# M_2_SoM_breakout_board_V1_0.net
KiCad netlist of a schematic drawn in EAGLE
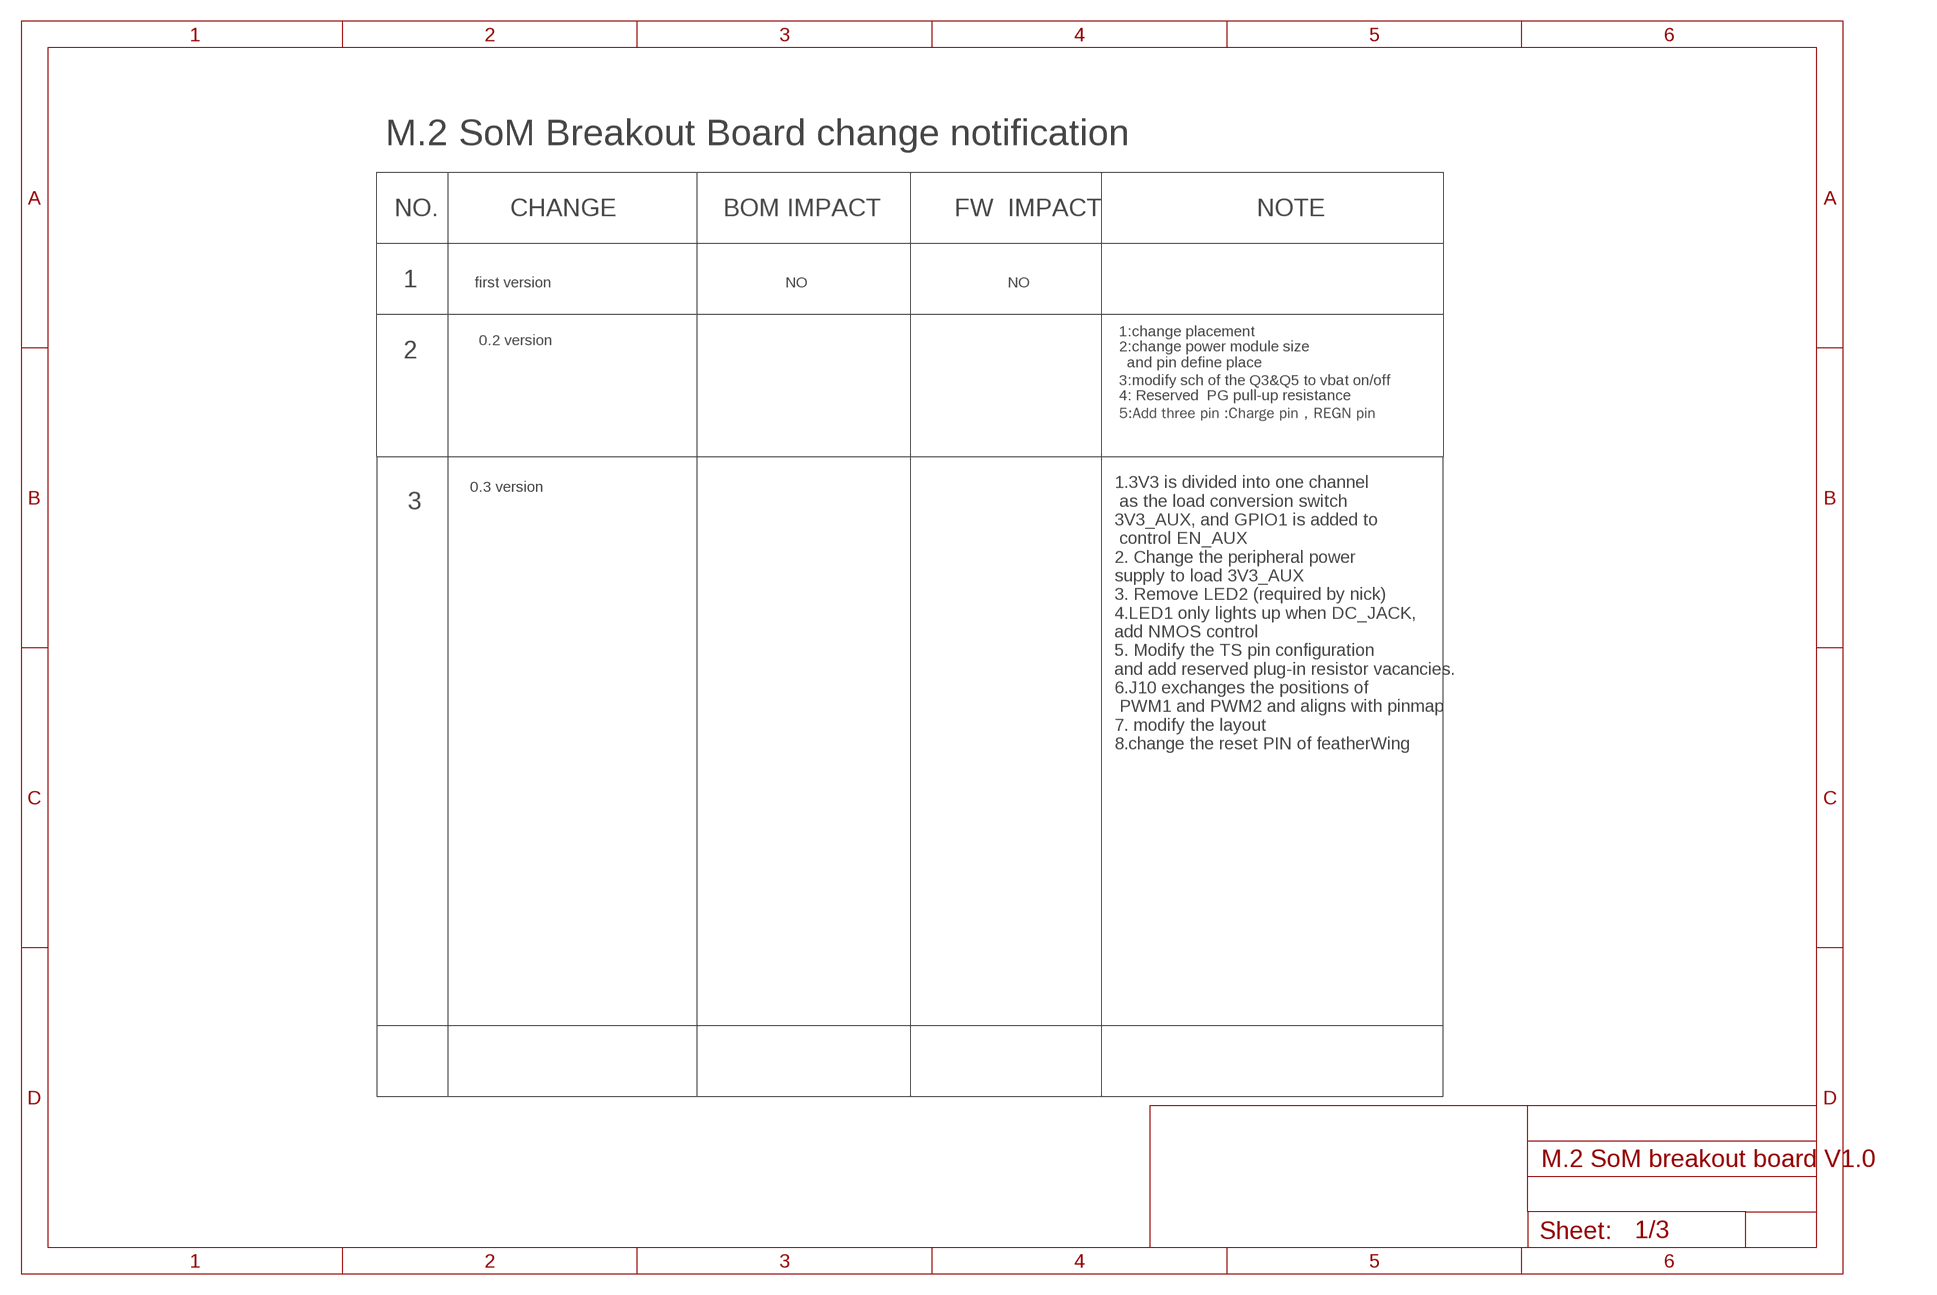
[diagram p0: schematic, sheet 1]
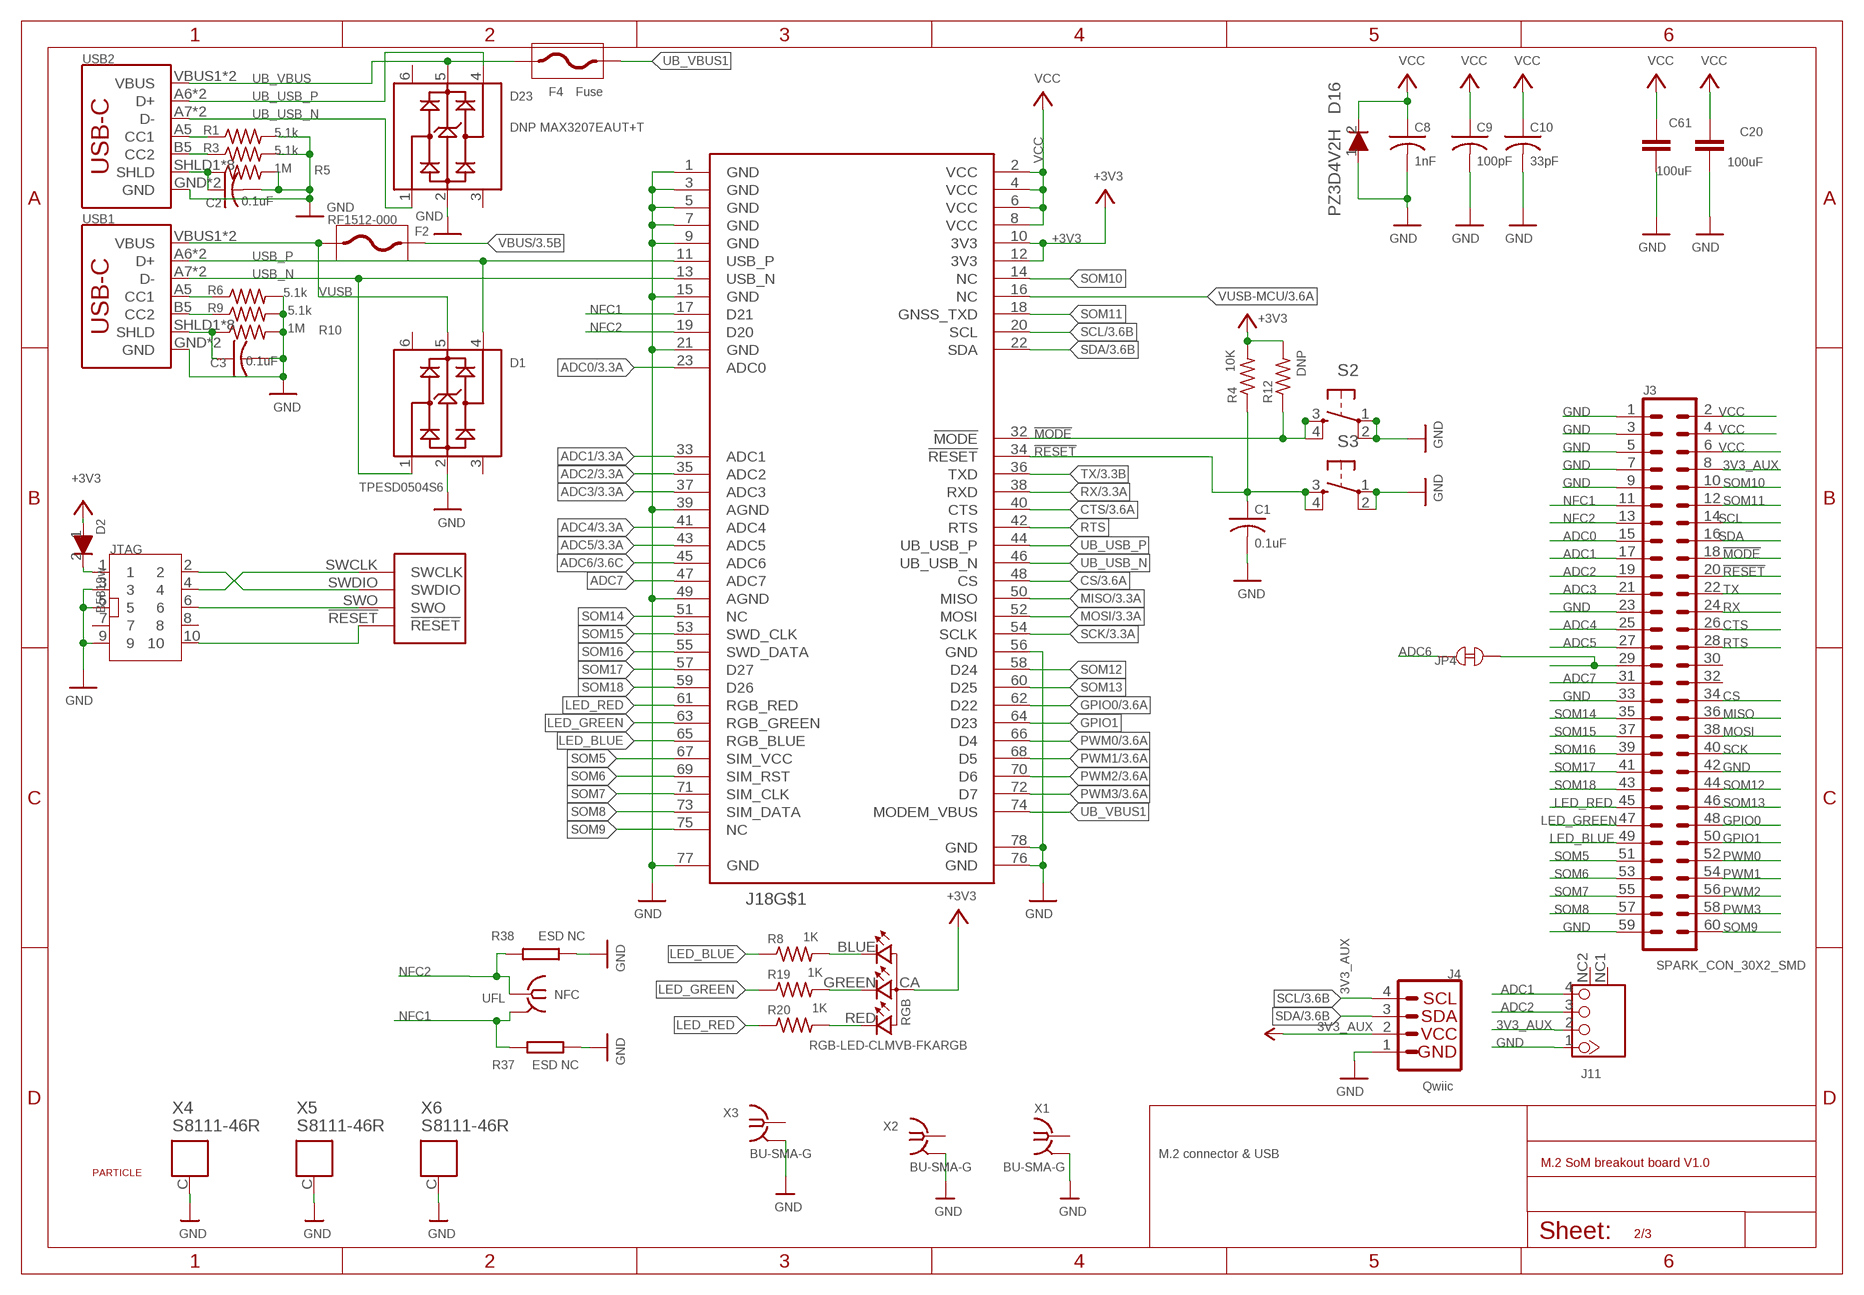
[diagram p1: schematic, sheet 2]
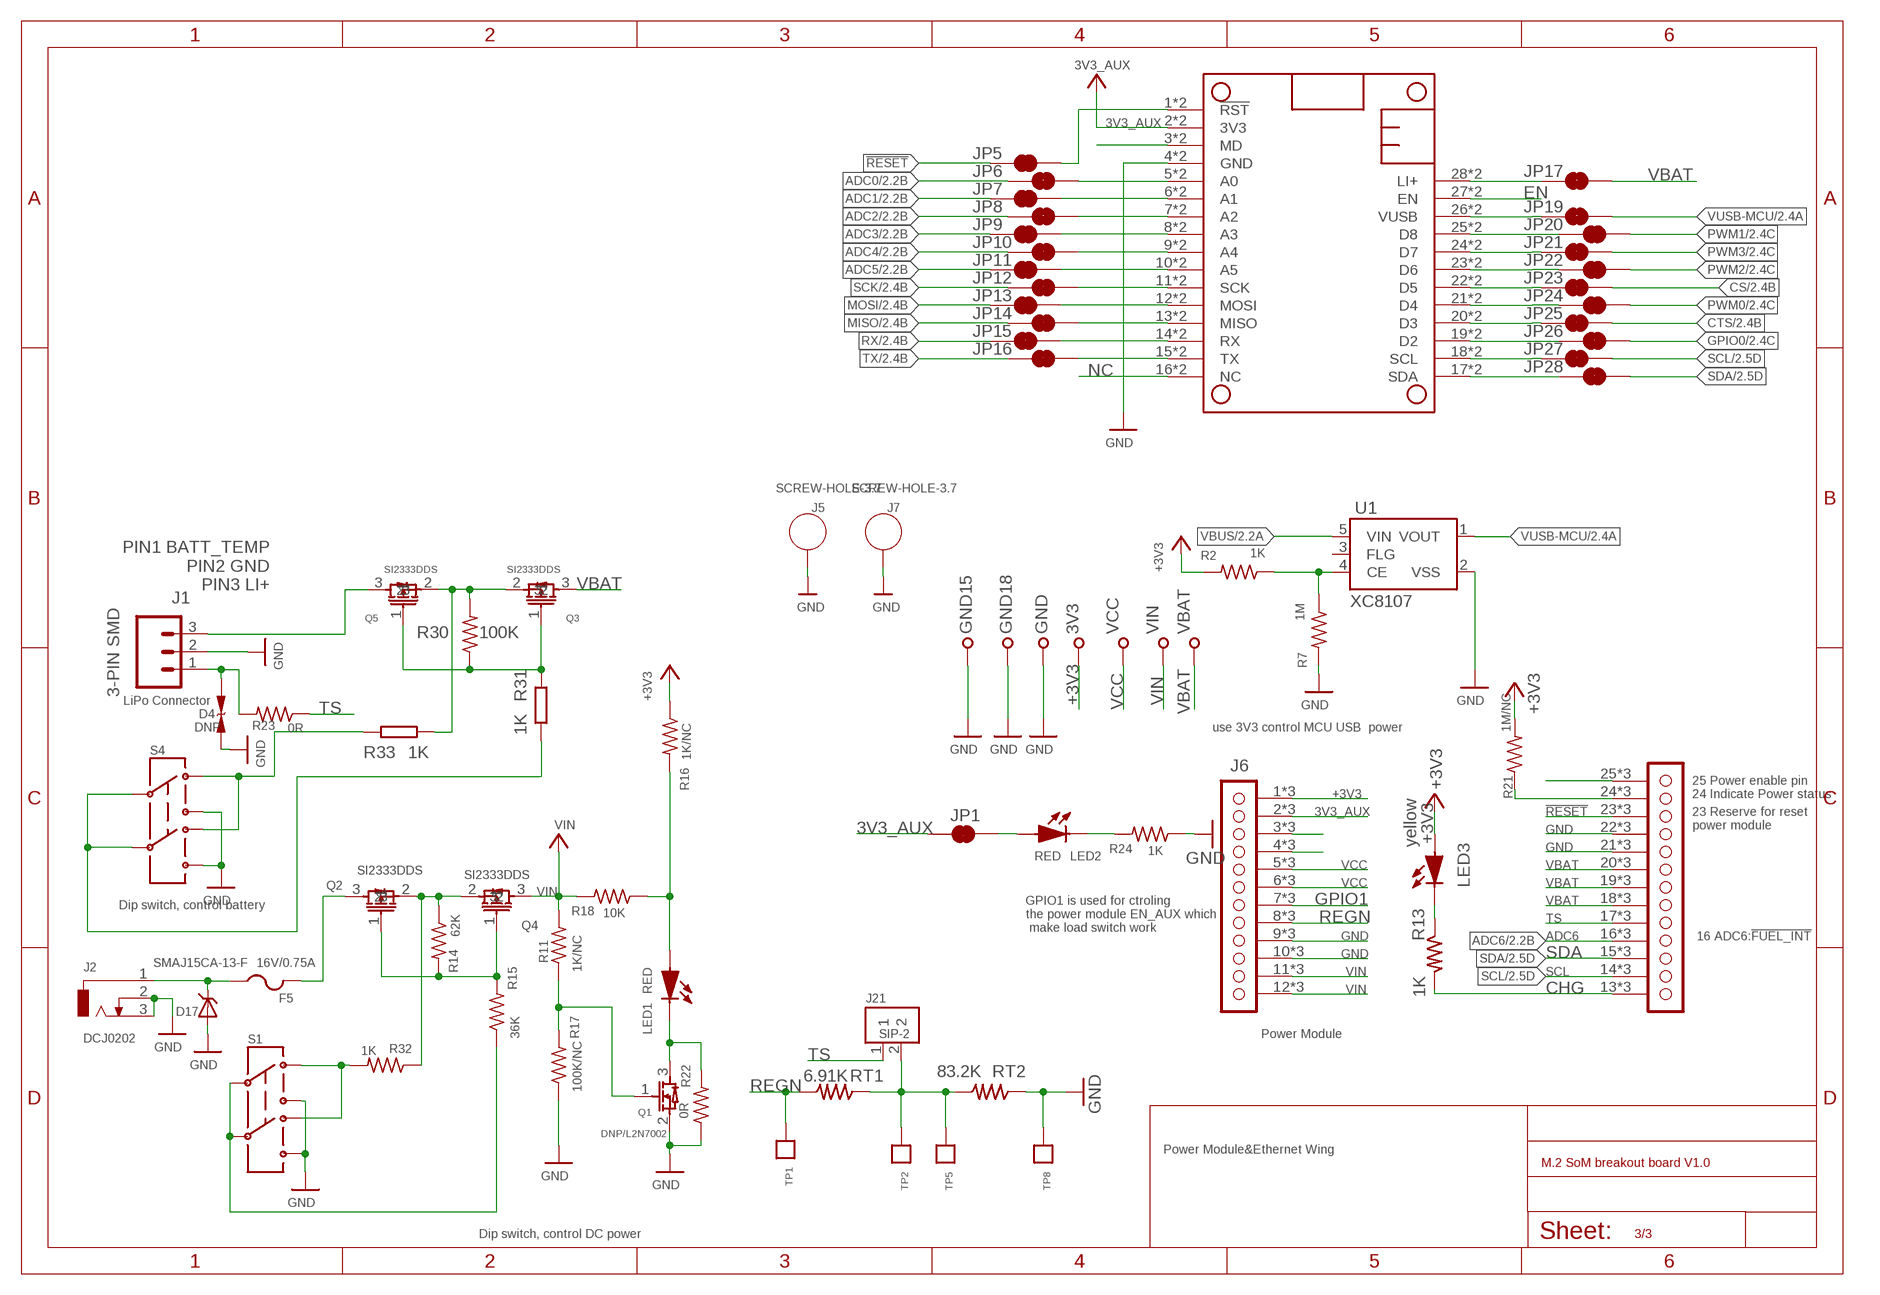
[diagram p2: schematic, sheet 3]

(export (version "E")
  (design (tool "Eeschema 10.0.6"))
  (components
    (comp (ref "C1")
      (value "0.1uF")
      (footprint "eagle-import:C0402_B")
      (libsource (lib "eagle-import") (part "C-US"))
    )
    (comp (ref "C2")
      (value "0.1uF")
      (footprint "eagle-import:C0402_B")
      (libsource (lib "eagle-import") (part "C-US"))
    )
    (comp (ref "C3")
      (value "0.1uF")
      (footprint "eagle-import:C0402_B")
      (libsource (lib "eagle-import") (part "C-US"))
    )
    (comp (ref "C8")
      (value "1nF")
      (footprint "eagle-import:C0402_B")
      (libsource (lib "eagle-import") (part "C-US"))
    )
    (comp (ref "C9")
      (value "100pF")
      (footprint "eagle-import:C0402_B")
      (libsource (lib "eagle-import") (part "C-US"))
    )
    (comp (ref "C10")
      (value "33pF")
      (footprint "eagle-import:C0402_B")
      (libsource (lib "eagle-import") (part "C-US"))
    )
    (comp (ref "C20")
      (value "100uF")
      (footprint "eagle-import:C1206K")
      (libsource (lib "eagle-import") (part "C-EUC1206K"))
    )
    (comp (ref "C61")
      (value "100uF")
      (footprint "eagle-import:C1206K")
      (libsource (lib "eagle-import") (part "C-EUC1206K"))
    )
    (comp (ref "D1")
      (value "TPESD0504S6")
      (footprint "eagle-import:SOT23-6")
      (fields (field (name "MFG") "MAXIM") (field (name "MPN") "MAX3207EAUT+T"))
      (libsource (lib "eagle-import") (part "MAX3207EAUT+T"))
    )
    (comp (ref "D2")
      (value "B5819w")
      (footprint "eagle-import:SOD-123")
      (libsource (lib "eagle-import") (part "DIODESOD123"))
    )
    (comp (ref "D16")
      (value "PZ3D4V2H")
      (footprint "eagle-import:SOD-323")
      (libsource (lib "eagle-import") (part "DIODESOD323"))
    )
    (comp (ref "D23")
      (value "DNP MAX3207EAUT+T")
      (footprint "eagle-import:SOT23-6")
      (fields (field (name "MFG") "MAXIM") (field (name "MPN") "MAX3207EAUT+T"))
      (libsource (lib "eagle-import") (part "MAX3207EAUT+T"))
    )
    (comp (ref "F2")
      (value "RF1512-000")
      (footprint "eagle-import:F0805")
      (libsource (lib "eagle-import") (part "FUSE"))
    )
    (comp (ref "F4")
      (value "Fuse")
      (footprint "eagle-import:F0805")
      (libsource (lib "eagle-import") (part "FUSE"))
    )
    (comp (ref "J3")
      (value "SPARK_CON_30X2_SMD")
      (footprint "eagle-import:SPARK_CON_30X2_SMD")
      (libsource (lib "eagle-import") (part "SPARK_CON_30X2_SMD"))
    )
    (comp (ref "J4")
      (value "QWIIC_CONNECTORJS-1MM")
      (footprint "eagle-import:1X04_1MM_RA")
      (libsource (lib "eagle-import") (part "QWIIC_CONNECTORJS-1MM"))
    )
    (comp (ref "J11")
      (value "WAFER-HY2.0-4PWB")
      (footprint "eagle-import:M.2-SOM-BREAKOUT-BOARD-V0.2-0228_WAFER-HY2.0-4PWB")
      (libsource (lib "eagle-import") (part "M.2-SOM-BREAKOUT-BOARD-V0.2-0228_WAFER-HY2.0-4PWB"))
    )
    (comp (ref "J18")
      (value "PARTICLE-STUDIOS_M_SERIES_M.2KEY")
      (footprint "eagle-import:PARTICLE-STUDIOS_PARTICLE_M.2EKEY_3.65MM_DRILL")
      (libsource (lib "eagle-import") (part "PARTICLE-STUDIOS_M_SERIES_M.2KEY"))
    )
    (comp (ref "JP4")
      (value "TP_SHORT")
      (footprint "eagle-import:TP_SHORT")
      (libsource (lib "eagle-import") (part "TP_SHORT"))
    )
    (comp (ref "JTAG")
      (value "CONN5X2")
      (footprint "eagle-import:CONN5X2_1.27")
      (fields (field (name "MFG") "KAWEEI") (field (name "MPN") "P6014A-M2GC-030-10"))
      (libsource (lib "eagle-import") (part "CONN5X2"))
    )
    (comp (ref "NFC")
      (value "UFL")
      (footprint "eagle-import:IPEX-20279-001E")
      (libsource (lib "eagle-import") (part "IPEX-20279-001E"))
    )
    (comp (ref "R1")
      (value "5.1k")
      (footprint "eagle-import:R0402_B")
      (libsource (lib "eagle-import") (part "R-US_"))
    )
    (comp (ref "R3")
      (value "5.1k")
      (footprint "eagle-import:R0402_B")
      (libsource (lib "eagle-import") (part "R-US_"))
    )
    (comp (ref "R4")
      (value "10K")
      (footprint "eagle-import:R0402_B")
      (libsource (lib "eagle-import") (part "R-US_"))
    )
    (comp (ref "R5")
      (value "1M")
      (footprint "eagle-import:R0402_B")
      (libsource (lib "eagle-import") (part "R-US_"))
    )
    (comp (ref "R6")
      (value "5.1k")
      (footprint "eagle-import:R0402_B")
      (libsource (lib "eagle-import") (part "R-US_"))
    )
    (comp (ref "R8")
      (value "1K")
      (footprint "eagle-import:R0402_B")
      (libsource (lib "eagle-import") (part "R-US_"))
    )
    (comp (ref "R9")
      (value "5.1k")
      (footprint "eagle-import:R0402_B")
      (libsource (lib "eagle-import") (part "R-US_"))
    )
    (comp (ref "R10")
      (value "1M")
      (footprint "eagle-import:R0402_B")
      (libsource (lib "eagle-import") (part "R-US_"))
    )
    (comp (ref "R12")
      (value "DNP")
      (footprint "eagle-import:R0402_B")
      (libsource (lib "eagle-import") (part "R-US_"))
    )
    (comp (ref "R19")
      (value "1K")
      (footprint "eagle-import:R0402_B")
      (libsource (lib "eagle-import") (part "R-US_"))
    )
    (comp (ref "R20")
      (value "1K")
      (footprint "eagle-import:R0402_B")
      (libsource (lib "eagle-import") (part "R-US_"))
    )
    (comp (ref "R37")
      (value "ESD NC")
      (footprint "eagle-import:R-0402S")
      (libsource (lib "eagle-import") (part "RES0402S"))
    )
    (comp (ref "R38")
      (value "ESD NC")
      (footprint "eagle-import:R-0402S")
      (libsource (lib "eagle-import") (part "RES0402S"))
    )
    (comp (ref "RGB")
      (value "RGB-LED-CLMVB-FKARGB")
      (footprint "eagle-import:PLCC4-2MM-RGB")
      (libsource (lib "eagle-import") (part "RGB-LED-CLMVB-FKARGB"))
    )
    (comp (ref "S2")
      (value "TAC_SWITCH")
      (footprint "eagle-import:TACTILE_SWITCH_4.2_3.2")
      (libsource (lib "eagle-import") (part "TAC_SWITCH"))
    )
    (comp (ref "S3")
      (value "TAC_SWITCH")
      (footprint "eagle-import:TACTILE_SWITCH_4.2_3.2")
      (libsource (lib "eagle-import") (part "TAC_SWITCH"))
    )
    (comp (ref "U$6")
      (value "PARTICLE-LOGO")
      (footprint "eagle-import:PARTICLE-LOGO")
      (libsource (lib "eagle-import") (part "PARTICLE-LOGO"))
    )
    (comp (ref "USB1")
      (value "USB_C16PIN")
      (footprint "eagle-import:USB-C-16P")
      (libsource (lib "eagle-import") (part "USB_C16PIN"))
    )
    (comp (ref "USB2")
      (value "USB_C16PIN")
      (footprint "eagle-import:USB-C-16P")
      (libsource (lib "eagle-import") (part "USB_C16PIN"))
    )
    (comp (ref "X1")
      (value "BU-SMA-G")
      (footprint "eagle-import:BU-SMA-G")
      (libsource (lib "eagle-import") (part "BU-SMA-G"))
    )
    (comp (ref "X2")
      (value "BU-SMA-G")
      (footprint "eagle-import:BU-SMA-G")
      (libsource (lib "eagle-import") (part "BU-SMA-G"))
    )
    (comp (ref "X3")
      (value "BU-SMA-G")
      (footprint "eagle-import:BU-SMA-G")
      (libsource (lib "eagle-import") (part "BU-SMA-G"))
    )
    (comp (ref "X4")
      (value "S8111-46R")
      (footprint "eagle-import:S8111-46R")
      (libsource (lib "eagle-import") (part "S8111-46R"))
    )
    (comp (ref "X5")
      (value "S8111-46R")
      (footprint "eagle-import:S8111-46R")
      (libsource (lib "eagle-import") (part "S8111-46R"))
    )
    (comp (ref "X6")
      (value "S8111-46R")
      (footprint "eagle-import:S8111-46R")
      (libsource (lib "eagle-import") (part "S8111-46R"))
    )
    (comp (ref "3V3")
      (value "TP-S2751-46R")
      (footprint "eagle-import:S2751-46R")
      (libsource (lib "eagle-import") (part "TP-S2751-46R"))
    )
    (comp (ref "D4")
      (value "DNP")
      (footprint "eagle-import:C0402")
      (libsource (lib "eagle-import") (part "ESD"))
    )
    (comp (ref "D17")
      (value "SMAJ15CA-13-F")
      (footprint "eagle-import:SMADIODE")
      (libsource (lib "eagle-import") (part "DIODE-ZENER"))
    )
    (comp (ref "F5")
      (value "16V/0.75A")
      (footprint "eagle-import:1812")
      (libsource (lib "eagle-import") (part "PTCFUSE-1812"))
    )
    (comp (ref "GND")
      (value "TP-S2751-46R")
      (footprint "eagle-import:S2751-46R")
      (libsource (lib "eagle-import") (part "TP-S2751-46R"))
    )
    (comp (ref "GND15")
      (value "TP-S2751-46R")
      (footprint "eagle-import:S2751-46R")
      (libsource (lib "eagle-import") (part "TP-S2751-46R"))
    )
    (comp (ref "GND18")
      (value "TP-S2751-46R")
      (footprint "eagle-import:S2751-46R")
      (libsource (lib "eagle-import") (part "TP-S2751-46R"))
    )
    (comp (ref "J1")
      (value "3-PIN SMD")
      (footprint "eagle-import:JST-3-SMD")
      (libsource (lib "eagle-import") (part "CONN_03JST-SMD"))
    )
    (comp (ref "J2")
      (value "DCJ0202")
      (footprint "eagle-import:DCJ0202")
      (libsource (lib "eagle-import") (part "DCJ0202"))
    )
    (comp (ref "J5")
      (value "SCREW-HOLE-3.7")
      (footprint "eagle-import:SCREW-HOLE-3.7")
      (libsource (lib "eagle-import") (part "SCREW-HOLE-3.7"))
    )
    (comp (ref "J6")
      (value "M.2-SOM-BREAKOUT-BOARD-V0.3_M.2-SOM-BREAKOUT-BOARD-V0.2-0228_PARTICLE-SZ_PARTICLE-POWER-MODULE")
      (footprint "eagle-import:M.2-SOM-BREAKOUT-BOARD-V0.3_M.2-SOM-BREAKOUT-BOARD-V0.2-0228_PARTICLE-SZ_PARTICLE-POWER-MODULE")
      (libsource (lib "eagle-import") (part "M.2-SOM-BREAKOUT-BOARD-V0.3_M.2-SOM-BREAKOUT-BOARD-V0.2-0228_PARTICLE-SZ_PARTICLE-POWER-MODULE"))
    )
    (comp (ref "J7")
      (value "SCREW-HOLE-3.7")
      (footprint "eagle-import:SCREW-HOLE-3.7")
      (libsource (lib "eagle-import") (part "SCREW-HOLE-3.7"))
    )
    (comp (ref "J21")
      (value "SIP-2")
      (footprint "eagle-import:SIP-2")
      (libsource (lib "eagle-import") (part "SIP-2"))
    )
    (comp (ref "JP1")
      (value "JUMPER-SMT_2_NC_TRACE_NO-SILK")
      (footprint "eagle-import:SMT-JUMPER_2_NC_TRACE_NO-SILK")
      (libsource (lib "eagle-import") (part "JUMPER-SMT_2_NC_TRACE_NO-SILK"))
    )
    (comp (ref "JP5")
      (value "JUMPER-SMT_2_NC_TRACE_NO-SILK")
      (footprint "eagle-import:SMT-JUMPER_2_NC_TRACE_NO-SILK")
      (libsource (lib "eagle-import") (part "JUMPER-SMT_2_NC_TRACE_NO-SILK"))
    )
    (comp (ref "JP6")
      (value "JUMPER-SMT_2_NC_TRACE_NO-SILK")
      (footprint "eagle-import:SMT-JUMPER_2_NC_TRACE_NO-SILK")
      (libsource (lib "eagle-import") (part "JUMPER-SMT_2_NC_TRACE_NO-SILK"))
    )
    (comp (ref "JP7")
      (value "JUMPER-SMT_2_NC_TRACE_NO-SILK")
      (footprint "eagle-import:SMT-JUMPER_2_NC_TRACE_NO-SILK")
      (libsource (lib "eagle-import") (part "JUMPER-SMT_2_NC_TRACE_NO-SILK"))
    )
    (comp (ref "JP8")
      (value "JUMPER-SMT_2_NC_TRACE_NO-SILK")
      (footprint "eagle-import:SMT-JUMPER_2_NC_TRACE_NO-SILK")
      (libsource (lib "eagle-import") (part "JUMPER-SMT_2_NC_TRACE_NO-SILK"))
    )
    (comp (ref "JP9")
      (value "JUMPER-SMT_2_NC_TRACE_NO-SILK")
      (footprint "eagle-import:SMT-JUMPER_2_NC_TRACE_NO-SILK")
      (libsource (lib "eagle-import") (part "JUMPER-SMT_2_NC_TRACE_NO-SILK"))
    )
    (comp (ref "JP10")
      (value "JUMPER-SMT_2_NC_TRACE_NO-SILK")
      (footprint "eagle-import:SMT-JUMPER_2_NC_TRACE_NO-SILK")
      (libsource (lib "eagle-import") (part "JUMPER-SMT_2_NC_TRACE_NO-SILK"))
    )
    (comp (ref "JP11")
      (value "JUMPER-SMT_2_NC_TRACE_NO-SILK")
      (footprint "eagle-import:SMT-JUMPER_2_NC_TRACE_NO-SILK")
      (libsource (lib "eagle-import") (part "JUMPER-SMT_2_NC_TRACE_NO-SILK"))
    )
    (comp (ref "JP12")
      (value "JUMPER-SMT_2_NC_TRACE_NO-SILK")
      (footprint "eagle-import:SMT-JUMPER_2_NC_TRACE_NO-SILK")
      (libsource (lib "eagle-import") (part "JUMPER-SMT_2_NC_TRACE_NO-SILK"))
    )
    (comp (ref "JP13")
      (value "JUMPER-SMT_2_NC_TRACE_NO-SILK")
      (footprint "eagle-import:SMT-JUMPER_2_NC_TRACE_NO-SILK")
      (libsource (lib "eagle-import") (part "JUMPER-SMT_2_NC_TRACE_NO-SILK"))
    )
    (comp (ref "JP14")
      (value "JUMPER-SMT_2_NC_TRACE_NO-SILK")
      (footprint "eagle-import:SMT-JUMPER_2_NC_TRACE_NO-SILK")
      (libsource (lib "eagle-import") (part "JUMPER-SMT_2_NC_TRACE_NO-SILK"))
    )
    (comp (ref "JP15")
      (value "JUMPER-SMT_2_NC_TRACE_NO-SILK")
      (footprint "eagle-import:SMT-JUMPER_2_NC_TRACE_NO-SILK")
      (libsource (lib "eagle-import") (part "JUMPER-SMT_2_NC_TRACE_NO-SILK"))
    )
    (comp (ref "JP16")
      (value "JUMPER-SMT_2_NC_TRACE_NO-SILK")
      (footprint "eagle-import:SMT-JUMPER_2_NC_TRACE_NO-SILK")
      (libsource (lib "eagle-import") (part "JUMPER-SMT_2_NC_TRACE_NO-SILK"))
    )
    (comp (ref "JP17")
      (value "JUMPER-SMT_2_NC_TRACE_NO-SILK")
      (footprint "eagle-import:SMT-JUMPER_2_NC_TRACE_NO-SILK")
      (libsource (lib "eagle-import") (part "JUMPER-SMT_2_NC_TRACE_NO-SILK"))
    )
    (comp (ref "JP19")
      (value "JUMPER-SMT_2_NC_TRACE_NO-SILK")
      (footprint "eagle-import:SMT-JUMPER_2_NC_TRACE_NO-SILK")
      (libsource (lib "eagle-import") (part "JUMPER-SMT_2_NC_TRACE_NO-SILK"))
    )
    (comp (ref "JP20")
      (value "JUMPER-SMT_2_NC_TRACE_NO-SILK")
      (footprint "eagle-import:SMT-JUMPER_2_NC_TRACE_NO-SILK")
      (libsource (lib "eagle-import") (part "JUMPER-SMT_2_NC_TRACE_NO-SILK"))
    )
    (comp (ref "JP21")
      (value "JUMPER-SMT_2_NC_TRACE_NO-SILK")
      (footprint "eagle-import:SMT-JUMPER_2_NC_TRACE_NO-SILK")
      (libsource (lib "eagle-import") (part "JUMPER-SMT_2_NC_TRACE_NO-SILK"))
    )
    (comp (ref "JP22")
      (value "JUMPER-SMT_2_NC_TRACE_NO-SILK")
      (footprint "eagle-import:SMT-JUMPER_2_NC_TRACE_NO-SILK")
      (libsource (lib "eagle-import") (part "JUMPER-SMT_2_NC_TRACE_NO-SILK"))
    )
    (comp (ref "JP23")
      (value "JUMPER-SMT_2_NC_TRACE_NO-SILK")
      (footprint "eagle-import:SMT-JUMPER_2_NC_TRACE_NO-SILK")
      (libsource (lib "eagle-import") (part "JUMPER-SMT_2_NC_TRACE_NO-SILK"))
    )
    (comp (ref "JP24")
      (value "JUMPER-SMT_2_NC_TRACE_NO-SILK")
      (footprint "eagle-import:SMT-JUMPER_2_NC_TRACE_NO-SILK")
      (libsource (lib "eagle-import") (part "JUMPER-SMT_2_NC_TRACE_NO-SILK"))
    )
    (comp (ref "JP25")
      (value "JUMPER-SMT_2_NC_TRACE_NO-SILK")
      (footprint "eagle-import:SMT-JUMPER_2_NC_TRACE_NO-SILK")
      (libsource (lib "eagle-import") (part "JUMPER-SMT_2_NC_TRACE_NO-SILK"))
    )
    (comp (ref "JP26")
      (value "JUMPER-SMT_2_NC_TRACE_NO-SILK")
      (footprint "eagle-import:SMT-JUMPER_2_NC_TRACE_NO-SILK")
      (libsource (lib "eagle-import") (part "JUMPER-SMT_2_NC_TRACE_NO-SILK"))
    )
    (comp (ref "JP27")
      (value "JUMPER-SMT_2_NC_TRACE_NO-SILK")
      (footprint "eagle-import:SMT-JUMPER_2_NC_TRACE_NO-SILK")
      (libsource (lib "eagle-import") (part "JUMPER-SMT_2_NC_TRACE_NO-SILK"))
    )
    (comp (ref "JP28")
      (value "JUMPER-SMT_2_NC_TRACE_NO-SILK")
      (footprint "eagle-import:SMT-JUMPER_2_NC_TRACE_NO-SILK")
      (libsource (lib "eagle-import") (part "JUMPER-SMT_2_NC_TRACE_NO-SILK"))
    )
    (comp (ref "LED1")
      (value "RED")
      (footprint "eagle-import:LED0603")
      (libsource (lib "eagle-import") (part "LED"))
    )
    (comp (ref "LED2")
      (value "RED")
      (footprint "eagle-import:LED0603")
      (libsource (lib "eagle-import") (part "LED"))
    )
    (comp (ref "LED3")
      (value "yellow")
      (footprint "eagle-import:LED0603")
      (libsource (lib "eagle-import") (part "LED"))
    )
    (comp (ref "MS1")
      (value "PARTICLE_MESH_SMTDUAL")
      (footprint "eagle-import:FEATHERWING_SMT2")
      (libsource (lib "eagle-import") (part "PARTICLE_MESH_SMTDUAL"))
    )
    (comp (ref "Q1")
      (value "DNP/L2N7002")
      (footprint "eagle-import:SOT323")
      (libsource (lib "eagle-import") (part "NMOSSOT323"))
    )
    (comp (ref "Q2")
      (value "SI2333DDS")
      (footprint "eagle-import:SOT-23")
      (libsource (lib "eagle-import") (part "PMOS"))
    )
    (comp (ref "Q3")
      (value "SI2333DDS")
      (footprint "eagle-import:SOT-23")
      (libsource (lib "eagle-import") (part "PMOS"))
    )
    (comp (ref "Q4")
      (value "SI2333DDS")
      (footprint "eagle-import:SOT-23")
      (libsource (lib "eagle-import") (part "PMOS"))
    )
    (comp (ref "Q5")
      (value "SI2333DDS")
      (footprint "eagle-import:SOT-23")
      (libsource (lib "eagle-import") (part "PMOS"))
    )
    (comp (ref "R2")
      (value "1K")
      (footprint "eagle-import:R0402_B")
      (libsource (lib "eagle-import") (part "R-US_"))
    )
    (comp (ref "R7")
      (value "1M")
      (footprint "eagle-import:R0402_B")
      (libsource (lib "eagle-import") (part "R-US_"))
    )
    (comp (ref "R11")
      (value "1K/NC")
      (footprint "eagle-import:R0402_B")
      (libsource (lib "eagle-import") (part "R-US_"))
    )
    (comp (ref "R13")
      (value "1K")
      (footprint "eagle-import:R-0402S")
      (libsource (lib "eagle-import") (part "particle SZ_RES0402S"))
    )
    (comp (ref "R14")
      (value "62K")
      (footprint "eagle-import:R0402_B")
      (libsource (lib "eagle-import") (part "R-US_"))
    )
    (comp (ref "R15")
      (value "36K")
      (footprint "eagle-import:R0402_B")
      (libsource (lib "eagle-import") (part "R-US_"))
    )
    (comp (ref "R16")
      (value "1K/NC")
      (footprint "eagle-import:R0402_B")
      (libsource (lib "eagle-import") (part "R-US_"))
    )
    (comp (ref "R17")
      (value "100K/NC")
      (footprint "eagle-import:R0402_B")
      (libsource (lib "eagle-import") (part "R-US_"))
    )
    (comp (ref "R18")
      (value "10K")
      (footprint "eagle-import:R0402_B")
      (libsource (lib "eagle-import") (part "R-US_"))
    )
    (comp (ref "R21")
      (value "1M/NC")
      (footprint "eagle-import:R0402_B")
      (libsource (lib "eagle-import") (part "R-US_"))
    )
    (comp (ref "R22")
      (value "0R")
      (footprint "eagle-import:R0402_B")
      (libsource (lib "eagle-import") (part "R-US_"))
    )
    (comp (ref "R23")
      (value "0R")
      (footprint "eagle-import:R0402_B")
      (libsource (lib "eagle-import") (part "R-US_"))
    )
    (comp (ref "R24")
      (value "1K")
      (footprint "eagle-import:R0402_B")
      (libsource (lib "eagle-import") (part "R-US_"))
    )
    (comp (ref "R30")
      (value "100K")
      (footprint "eagle-import:R0603_P")
      (libsource (lib "eagle-import") (part "RES_0603100K_"))
    )
    (comp (ref "R31")
      (value "1K")
      (footprint "eagle-import:R-0402S")
      (libsource (lib "eagle-import") (part "RES0402S"))
    )
    (comp (ref "R32")
      (value "1K")
      (footprint "eagle-import:R0402_B")
      (libsource (lib "eagle-import") (part "R-US_"))
    )
    (comp (ref "R33")
      (value "1K")
      (footprint "eagle-import:R-0402S")
      (libsource (lib "eagle-import") (part "RES0402S"))
    )
    (comp (ref "RT1")
      (value "6.91K")
      (footprint "eagle-import:R-0603A")
      (libsource (lib "eagle-import") (part "RESR0603A"))
    )
    (comp (ref "RT2")
      (value "83.2K")
      (footprint "eagle-import:R-0603A")
      (libsource (lib "eagle-import") (part "RESR0603A"))
    )
    (comp (ref "S1")
      (value "SWITCH-DPDT")
      (footprint "eagle-import:SWITCH-2.5X3.2-6")
      (libsource (lib "eagle-import") (part "SWITCH-DPDT"))
    )
    (comp (ref "S4")
      (value "SWITCH-DPDT")
      (footprint "eagle-import:SWITCH-2.5X3.2-6")
      (libsource (lib "eagle-import") (part "SWITCH-DPDT"))
    )
    (comp (ref "TP1")
      (value "TPTPEB")
      (footprint "eagle-import:TPEB")
      (libsource (lib "eagle-import") (part "TPTPEB"))
    )
    (comp (ref "TP2")
      (value "TPTPEB")
      (footprint "eagle-import:TPEB")
      (libsource (lib "eagle-import") (part "TPTPEB"))
    )
    (comp (ref "TP5")
      (value "TPTPEB")
      (footprint "eagle-import:TPEB")
      (libsource (lib "eagle-import") (part "TPTPEB"))
    )
    (comp (ref "TP8")
      (value "TPTPEB")
      (footprint "eagle-import:TPEB")
      (libsource (lib "eagle-import") (part "TPTPEB"))
    )
    (comp (ref "U1")
      (value "XC8107")
      (footprint "eagle-import:SOT25")
      (libsource (lib "eagle-import") (part "XC8107SOT25"))
    )
    (comp (ref "VBAT")
      (value "TP-S2751-46R")
      (footprint "eagle-import:S2751-46R")
      (libsource (lib "eagle-import") (part "TP-S2751-46R"))
    )
    (comp (ref "VCC")
      (value "TP-S2751-46R")
      (footprint "eagle-import:S2751-46R")
      (libsource (lib "eagle-import") (part "TP-S2751-46R"))
    )
    (comp (ref "VIN")
      (value "TP-S2751-46R")
      (footprint "eagle-import:S2751-46R")
      (libsource (lib "eagle-import") (part "TP-S2751-46R"))
    )
  )
  (nets
    (net (code "1") (name "+3V3") (class "Default")
      (node (ref "3V3") (pin "1") (pinfunction "TP_1") (pintype "bidirectional"))
      (node (ref "D2") (pin "1") (pinfunction "P$1_1") (pintype "bidirectional"))
      (node (ref "J18") (pin "10") (pinfunction "3V3_10") (pintype "power_in"))
      (node (ref "J18") (pin "12") (pinfunction "3V3_12") (pintype "power_in"))
      (node (ref "J6") (pin "1") (pinfunction "3V3_1") (pintype "passive"))
      (node (ref "J6") (pin "@1") (pinfunction "3V3_@1") (pintype "passive"))
      (node (ref "J6") (pin "P$1") (pinfunction "3V3_P$1") (pintype "passive"))
      (node (ref "LED3") (pin "1") (pinfunction "A_1") (pintype "bidirectional"))
      (node (ref "R12") (pin "2") (pinfunction "2_2") (pintype "passive"))
      (node (ref "R16") (pin "1") (pinfunction "1_1") (pintype "passive"))
      (node (ref "R2") (pin "2") (pinfunction "2_2") (pintype "passive"))
      (node (ref "R21") (pin "2") (pinfunction "2_2") (pintype "passive"))
      (node (ref "R4") (pin "2") (pinfunction "2_2") (pintype "passive"))
      (node (ref "RGB") (pin "CA") (pinfunction "1_CA") (pintype "passive"))
    )
    (net (code "2") (name "3V3_AUX") (class "Default")
      (node (ref "J11") (pin "2") (pinfunction "2_2") (pintype "bidirectional"))
      (node (ref "J3") (pin "8") (pinfunction "8_8") (pintype "passive"))
      (node (ref "J4") (pin "2") (pinfunction "2_2") (pintype "power_in"))
      (node (ref "J6") (pin "2") (pinfunction "3V3_2") (pintype "passive"))
      (node (ref "J6") (pin "@2") (pinfunction "3V3_@2") (pintype "passive"))
      (node (ref "J6") (pin "P$2") (pinfunction "3V3_P$2") (pintype "passive"))
      (node (ref "JP1") (pin "1") (pinfunction "1_1") (pintype "passive"))
      (node (ref "MS1") (pin "2") (pinfunction "3V3_2") (pintype "power_in"))
      (node (ref "MS1") (pin "2'") (pinfunction "3V3_2'") (pintype "power_in"))
    )
    (net (code "3") (name "ADC0") (class "Default")
      (node (ref "J18") (pin "23") (pinfunction "ADC0_23") (pintype "bidirectional"))
      (node (ref "J3") (pin "15") (pinfunction "15_15") (pintype "passive"))
      (node (ref "JP6") (pin "1") (pinfunction "1_1") (pintype "passive"))
    )
    (net (code "4") (name "ADC1") (class "Default")
      (node (ref "J11") (pin "4") (pinfunction "4_4") (pintype "bidirectional"))
      (node (ref "J18") (pin "33") (pinfunction "ADC1_33") (pintype "bidirectional"))
      (node (ref "J3") (pin "17") (pinfunction "17_17") (pintype "passive"))
      (node (ref "JP7") (pin "1") (pinfunction "1_1") (pintype "passive"))
    )
    (net (code "5") (name "ADC2") (class "Default")
      (node (ref "J11") (pin "3") (pinfunction "3_3") (pintype "bidirectional"))
      (node (ref "J18") (pin "35") (pinfunction "ADC2_35") (pintype "bidirectional"))
      (node (ref "J3") (pin "19") (pinfunction "19_19") (pintype "passive"))
      (node (ref "JP8") (pin "1") (pinfunction "1_1") (pintype "passive"))
    )
    (net (code "6") (name "ADC3") (class "Default")
      (node (ref "J18") (pin "37") (pinfunction "ADC3_37") (pintype "bidirectional"))
      (node (ref "J3") (pin "21") (pinfunction "21_21") (pintype "passive"))
      (node (ref "JP9") (pin "1") (pinfunction "1_1") (pintype "passive"))
    )
    (net (code "7") (name "ADC4") (class "Default")
      (node (ref "J18") (pin "41") (pinfunction "ADC4_41") (pintype "bidirectional"))
      (node (ref "J3") (pin "25") (pinfunction "25_25") (pintype "passive"))
      (node (ref "JP10") (pin "1") (pinfunction "1_1") (pintype "passive"))
    )
    (net (code "8") (name "ADC5") (class "Default")
      (node (ref "J18") (pin "43") (pinfunction "ADC5_43") (pintype "bidirectional"))
      (node (ref "J3") (pin "27") (pinfunction "27_27") (pintype "passive"))
      (node (ref "JP11") (pin "1") (pinfunction "1_1") (pintype "passive"))
    )
    (net (code "9") (name "ADC6") (class "Default")
      (node (ref "J18") (pin "45") (pinfunction "ADC6_45") (pintype "bidirectional"))
      (node (ref "J6") (pin "16") (pinfunction "~{FUEL-INT}_16") (pintype "passive"))
      (node (ref "J6") (pin "@16") (pinfunction "~{FUEL-INT}_@16") (pintype "passive"))
      (node (ref "J6") (pin "P$16") (pinfunction "~{FUEL-INT}_P$16") (pintype "passive"))
      (node (ref "JP4") (pin "2") (pinfunction "2_2") (pintype "bidirectional"))
    )
    (net (code "10") (name "ADC7") (class "Default")
      (node (ref "J18") (pin "47") (pinfunction "ADC7_47") (pintype "bidirectional"))
      (node (ref "J3") (pin "31") (pinfunction "31_31") (pintype "passive"))
    )
    (net (code "11") (name "CHG") (class "Default")
      (node (ref "J6") (pin "13") (pinfunction "CHG_13") (pintype "passive"))
      (node (ref "J6") (pin "@13") (pinfunction "CHG_@13") (pintype "passive"))
      (node (ref "J6") (pin "P$13") (pinfunction "CHG_P$13") (pintype "passive"))
      (node (ref "R13") (pin "2") (pinfunction "2_2") (pintype "bidirectional"))
    )
    (net (code "12") (name "CS") (class "Default")
      (node (ref "J18") (pin "48") (pinfunction "CS_48") (pintype "bidirectional"))
      (node (ref "J3") (pin "34") (pinfunction "34_34") (pintype "passive"))
      (node (ref "JP23") (pin "2") (pinfunction "2_2") (pintype "passive"))
    )
    (net (code "13") (name "CTS") (class "Default")
      (node (ref "J18") (pin "40") (pinfunction "CTS_40") (pintype "bidirectional"))
      (node (ref "J3") (pin "26") (pinfunction "26_26") (pintype "passive"))
      (node (ref "JP25") (pin "2") (pinfunction "2_2") (pintype "passive"))
    )
    (net (code "14") (name "EN") (class "Default")
      (node (ref "MS1") (pin "27") (pinfunction "EN_27") (pintype "passive"))
      (node (ref "MS1") (pin "27'") (pinfunction "EN_27'") (pintype "passive"))
    )
    (net (code "15") (name "GND") (class "Default")
      (node (ref "C1") (pin "2") (pinfunction "2_2") (pintype "passive"))
      (node (ref "C10") (pin "2") (pinfunction "2_2") (pintype "passive"))
      (node (ref "C2") (pin "2") (pinfunction "2_2") (pintype "passive"))
      (node (ref "C20") (pin "2") (pinfunction "2_2") (pintype "passive"))
      (node (ref "C3") (pin "2") (pinfunction "2_2") (pintype "passive"))
      (node (ref "C61") (pin "2") (pinfunction "2_2") (pintype "passive"))
      (node (ref "C8") (pin "2") (pinfunction "2_2") (pintype "passive"))
      (node (ref "C9") (pin "2") (pinfunction "2_2") (pintype "passive"))
      (node (ref "D1") (pin "2") (pinfunction "2_2") (pintype "bidirectional"))
      (node (ref "D16") (pin "1") (pinfunction "P$1_1") (pintype "bidirectional"))
      (node (ref "D17") (pin "A") (pinfunction "A_A") (pintype "passive"))
      (node (ref "D23") (pin "2") (pinfunction "2_2") (pintype "bidirectional"))
      (node (ref "D4") (pin "1") (pinfunction "1_1") (pintype "bidirectional"))
      (node (ref "GND") (pin "1") (pinfunction "TP_1") (pintype "bidirectional"))
      (node (ref "GND15") (pin "1") (pinfunction "TP_1") (pintype "bidirectional"))
      (node (ref "GND18") (pin "1") (pinfunction "TP_1") (pintype "bidirectional"))
      (node (ref "J1") (pin "2") (pinfunction "2_2") (pintype "passive"))
      (node (ref "J11") (pin "1") (pinfunction "1_1") (pintype "bidirectional"))
      (node (ref "J18") (pin "1") (pinfunction "GND_1") (pintype "power_in"))
      (node (ref "J18") (pin "15") (pinfunction "GND_15") (pintype "power_in"))
      (node (ref "J18") (pin "21") (pinfunction "GND_21") (pintype "power_in"))
      (node (ref "J18") (pin "3") (pinfunction "GND_3") (pintype "power_in"))
      (node (ref "J18") (pin "39") (pinfunction "AGND_39") (pintype "power_in"))
      (node (ref "J18") (pin "49") (pinfunction "AGND_49") (pintype "power_in"))
      (node (ref "J18") (pin "5") (pinfunction "GND_5") (pintype "power_in"))
      (node (ref "J18") (pin "56") (pinfunction "GND_56") (pintype "power_in"))
      (node (ref "J18") (pin "7") (pinfunction "GND_7") (pintype "power_in"))
      (node (ref "J18") (pin "76") (pinfunction "GND_76") (pintype "power_in"))
      (node (ref "J18") (pin "77") (pinfunction "GND_77") (pintype "power_in"))
      (node (ref "J18") (pin "78") (pinfunction "GND_78") (pintype "power_in"))
      (node (ref "J18") (pin "9") (pinfunction "GND_9") (pintype "power_in"))
      (node (ref "J2") (pin "2") (pinfunction "2_2") (pintype "passive"))
      (node (ref "J2") (pin "3") (pinfunction "3_3") (pintype "passive"))
      (node (ref "J3") (pin "1") (pinfunction "1_1") (pintype "passive"))
      (node (ref "J3") (pin "23") (pinfunction "23_23") (pintype "passive"))
      (node (ref "J3") (pin "3") (pinfunction "3_3") (pintype "passive"))
      (node (ref "J3") (pin "33") (pinfunction "33_33") (pintype "passive"))
      (node (ref "J3") (pin "42") (pinfunction "42_42") (pintype "passive"))
      (node (ref "J3") (pin "5") (pinfunction "5_5") (pintype "passive"))
      (node (ref "J3") (pin "59") (pinfunction "59_59") (pintype "passive"))
      (node (ref "J3") (pin "7") (pinfunction "7_7") (pintype "passive"))
      (node (ref "J3") (pin "9") (pinfunction "9_9") (pintype "passive"))
      (node (ref "J4") (pin "1") (pinfunction "1_1") (pintype "power_in"))
      (node (ref "J5") (pin "P$1") (pinfunction "GND_P$1") (pintype "bidirectional"))
      (node (ref "J6") (pin "10") (pinfunction "GND_10") (pintype "passive"))
      (node (ref "J6") (pin "21") (pinfunction "GND_21") (pintype "passive"))
      (node (ref "J6") (pin "22") (pinfunction "GND_22") (pintype "passive"))
      (node (ref "J6") (pin "9") (pinfunction "GND_9") (pintype "passive"))
      (node (ref "J6") (pin "@10") (pinfunction "GND_@10") (pintype "passive"))
      (node (ref "J6") (pin "@21") (pinfunction "GND_@21") (pintype "passive"))
      (node (ref "J6") (pin "@22") (pinfunction "GND_@22") (pintype "passive"))
      (node (ref "J6") (pin "@9") (pinfunction "GND_@9") (pintype "passive"))
      (node (ref "J6") (pin "P$10") (pinfunction "GND_P$10") (pintype "passive"))
      (node (ref "J6") (pin "P$21") (pinfunction "GND_P$21") (pintype "passive"))
      (node (ref "J6") (pin "P$22") (pinfunction "GND_P$22") (pintype "passive"))
      (node (ref "J6") (pin "P$9") (pinfunction "GND_P$9") (pintype "passive"))
      (node (ref "J7") (pin "P$1") (pinfunction "GND_P$1") (pintype "bidirectional"))
      (node (ref "JTAG") (pin "3") (pinfunction "3_3") (pintype "bidirectional"))
      (node (ref "JTAG") (pin "5") (pinfunction "5_5") (pintype "bidirectional"))
      (node (ref "JTAG") (pin "9") (pinfunction "9_9") (pintype "bidirectional"))
      (node (ref "MS1") (pin "4") (pinfunction "GND_4") (pintype "power_in"))
      (node (ref "MS1") (pin "4'") (pinfunction "GND_4'") (pintype "power_in"))
      (node (ref "Q1") (pin "2") (pinfunction "2_2") (pintype "bidirectional"))
      (node (ref "R1") (pin "2") (pinfunction "2_2") (pintype "passive"))
      (node (ref "R10") (pin "2") (pinfunction "2_2") (pintype "passive"))
      (node (ref "R17") (pin "1") (pinfunction "1_1") (pintype "passive"))
      (node (ref "R22") (pin "1") (pinfunction "1_1") (pintype "passive"))
      (node (ref "R24") (pin "1") (pinfunction "1_1") (pintype "passive"))
      (node (ref "R3") (pin "2") (pinfunction "2_2") (pintype "passive"))
      (node (ref "R37") (pin "2") (pinfunction "2_2") (pintype "bidirectional"))
      (node (ref "R38") (pin "1") (pinfunction "1_1") (pintype "bidirectional"))
      (node (ref "R5") (pin "2") (pinfunction "2_2") (pintype "passive"))
      (node (ref "R6") (pin "2") (pinfunction "2_2") (pintype "passive"))
      (node (ref "R7") (pin "2") (pinfunction "2_2") (pintype "passive"))
      (node (ref "R9") (pin "2") (pinfunction "2_2") (pintype "passive"))
      (node (ref "RT2") (pin "1") (pinfunction "1_1") (pintype "bidirectional"))
      (node (ref "S1") (pin "3") (pinfunction "3_3") (pintype "bidirectional"))
      (node (ref "S1") (pin "6") (pinfunction "6_6") (pintype "bidirectional"))
      (node (ref "S2") (pin "1") (pinfunction "1_1") (pintype "passive"))
      (node (ref "S2") (pin "2") (pinfunction "2_2") (pintype "passive"))
      (node (ref "S3") (pin "1") (pinfunction "1_1") (pintype "passive"))
      (node (ref "S3") (pin "2") (pinfunction "2_2") (pintype "passive"))
      (node (ref "S4") (pin "3") (pinfunction "3_3") (pintype "bidirectional"))
      (node (ref "S4") (pin "6") (pinfunction "6_6") (pintype "bidirectional"))
      (node (ref "TP8") (pin "1") (pinfunction "1_1") (pintype "bidirectional"))
      (node (ref "U1") (pin "2") (pinfunction "VSS_2") (pintype "power_in"))
      (node (ref "USB1") (pin "GND") (pinfunction "GND_GND") (pintype "bidirectional"))
      (node (ref "USB1") (pin "GND2") (pinfunction "GND_GND2") (pintype "bidirectional"))
      (node (ref "USB2") (pin "GND") (pinfunction "GND_GND") (pintype "bidirectional"))
      (node (ref "USB2") (pin "GND2") (pinfunction "GND_GND2") (pintype "bidirectional"))
      (node (ref "X1") (pin "2") (pinfunction "2_2") (pintype "passive"))
      (node (ref "X1") (pin "3") (pinfunction "2_3") (pintype "passive"))
      (node (ref "X1") (pin "4") (pinfunction "2_4") (pintype "passive"))
      (node (ref "X1") (pin "5") (pinfunction "2_5") (pintype "passive"))
      (node (ref "X2") (pin "2") (pinfunction "2_2") (pintype "passive"))
      (node (ref "X2") (pin "3") (pinfunction "2_3") (pintype "passive"))
      (node (ref "X2") (pin "4") (pinfunction "2_4") (pintype "passive"))
      (node (ref "X2") (pin "5") (pinfunction "2_5") (pintype "passive"))
      (node (ref "X3") (pin "2") (pinfunction "2_2") (pintype "passive"))
      (node (ref "X3") (pin "3") (pinfunction "2_3") (pintype "passive"))
      (node (ref "X3") (pin "4") (pinfunction "2_4") (pintype "passive"))
      (node (ref "X3") (pin "5") (pinfunction "2_5") (pintype "passive"))
      (node (ref "X4") (pin "C") (pinfunction "C_C") (pintype "power_in"))
      (node (ref "X5") (pin "C") (pinfunction "C_C") (pintype "power_in"))
      (node (ref "X6") (pin "C") (pinfunction "C_C") (pintype "power_in"))
    )
    (net (code "16") (name "GPIO0") (class "Default")
      (node (ref "J18") (pin "62") (pinfunction "D22_62") (pintype "bidirectional"))
      (node (ref "J3") (pin "48") (pinfunction "48_48") (pintype "passive"))
      (node (ref "JP26") (pin "2") (pinfunction "2_2") (pintype "passive"))
    )
    (net (code "17") (name "GPIO1") (class "Default")
      (node (ref "J18") (pin "64") (pinfunction "D23_64") (pintype "bidirectional"))
      (node (ref "J3") (pin "50") (pinfunction "50_50") (pintype "passive"))
      (node (ref "J6") (pin "7") (pinfunction "REGN_7") (pintype "passive"))
      (node (ref "J6") (pin "@7") (pinfunction "REGN_@7") (pintype "passive"))
      (node (ref "J6") (pin "P$7") (pinfunction "REGN_P$7") (pintype "passive"))
    )
    (net (code "18") (name "LED_BLUE") (class "Default")
      (node (ref "J18") (pin "65") (pinfunction "RGB_BLUE_65") (pintype "bidirectional"))
      (node (ref "J3") (pin "49") (pinfunction "49_49") (pintype "passive"))
      (node (ref "R8") (pin "1") (pinfunction "1_1") (pintype "passive"))
    )
    (net (code "19") (name "LED_GREEN") (class "Default")
      (node (ref "J18") (pin "63") (pinfunction "RGB_GREEN_63") (pintype "bidirectional"))
      (node (ref "J3") (pin "47") (pinfunction "47_47") (pintype "passive"))
      (node (ref "R19") (pin "1") (pinfunction "1_1") (pintype "passive"))
    )
    (net (code "20") (name "LED_RED") (class "Default")
      (node (ref "J18") (pin "61") (pinfunction "RGB_RED_61") (pintype "bidirectional"))
      (node (ref "J3") (pin "45") (pinfunction "45_45") (pintype "passive"))
      (node (ref "R20") (pin "1") (pinfunction "1_1") (pintype "passive"))
    )
    (net (code "21") (name "MISO") (class "Default")
      (node (ref "J18") (pin "50") (pinfunction "MISO_50") (pintype "bidirectional"))
      (node (ref "J3") (pin "36") (pinfunction "36_36") (pintype "passive"))
      (node (ref "JP14") (pin "1") (pinfunction "1_1") (pintype "passive"))
    )
    (net (code "22") (name "MOSI") (class "Default")
      (node (ref "J18") (pin "52") (pinfunction "MOSI_52") (pintype "bidirectional"))
      (node (ref "J3") (pin "38") (pinfunction "38_38") (pintype "passive"))
      (node (ref "JP13") (pin "1") (pinfunction "1_1") (pintype "passive"))
    )
    (net (code "23") (name "NC") (class "Default")
      (node (ref "MS1") (pin "16") (pinfunction "NC_16") (pintype "passive"))
      (node (ref "MS1") (pin "16'") (pinfunction "NC_16'") (pintype "passive"))
    )
    (net (code "24") (name "NFC1") (class "Default")
      (node (ref "J18") (pin "17") (pinfunction "D21_17") (pintype "bidirectional"))
      (node (ref "J3") (pin "11") (pinfunction "11_11") (pintype "passive"))
      (node (ref "NFC") (pin "2@1") (pinfunction "GND_2@1") (pintype "passive"))
      (node (ref "NFC") (pin "2@2") (pinfunction "GND_2@2") (pintype "passive"))
      (node (ref "R37") (pin "1") (pinfunction "1_1") (pintype "bidirectional"))
    )
    (net (code "25") (name "NFC2") (class "Default")
      (node (ref "J18") (pin "19") (pinfunction "D20_19") (pintype "bidirectional"))
      (node (ref "J3") (pin "13") (pinfunction "13_13") (pintype "passive"))
      (node (ref "NFC") (pin "1") (pinfunction "1_1") (pintype "passive"))
      (node (ref "R38") (pin "2") (pinfunction "2_2") (pintype "bidirectional"))
    )
    (net (code "26") (name "Net-(C2-Pad1)") (class "Default")
      (node (ref "C2") (pin "1") (pinfunction "1_1") (pintype "passive"))
      (node (ref "R5") (pin "1") (pinfunction "1_1") (pintype "passive"))
      (node (ref "USB2") (pin "SHLD1") (pinfunction "SHLD_SHLD1") (pintype "bidirectional"))
      (node (ref "USB2") (pin "SHLD2") (pinfunction "SHLD_SHLD2") (pintype "bidirectional"))
      (node (ref "USB2") (pin "SHLD3") (pinfunction "SHLD_SHLD3") (pintype "bidirectional"))
      (node (ref "USB2") (pin "SHLD4") (pinfunction "SHLD_SHLD4") (pintype "bidirectional"))
      (node (ref "USB2") (pin "SHLD5") (pinfunction "SHLD_SHLD5") (pintype "bidirectional"))
      (node (ref "USB2") (pin "SHLD6") (pinfunction "SHLD_SHLD6") (pintype "bidirectional"))
      (node (ref "USB2") (pin "SHLD7") (pinfunction "SHLD_SHLD7") (pintype "bidirectional"))
      (node (ref "USB2") (pin "SHLD8") (pinfunction "SHLD_SHLD8") (pintype "bidirectional"))
    )
    (net (code "27") (name "Net-(C3-Pad1)") (class "Default")
      (node (ref "C3") (pin "1") (pinfunction "1_1") (pintype "passive"))
      (node (ref "R10") (pin "1") (pinfunction "1_1") (pintype "passive"))
      (node (ref "USB1") (pin "SHLD1") (pinfunction "SHLD_SHLD1") (pintype "bidirectional"))
      (node (ref "USB1") (pin "SHLD2") (pinfunction "SHLD_SHLD2") (pintype "bidirectional"))
      (node (ref "USB1") (pin "SHLD3") (pinfunction "SHLD_SHLD3") (pintype "bidirectional"))
      (node (ref "USB1") (pin "SHLD4") (pinfunction "SHLD_SHLD4") (pintype "bidirectional"))
      (node (ref "USB1") (pin "SHLD5") (pinfunction "SHLD_SHLD5") (pintype "bidirectional"))
      (node (ref "USB1") (pin "SHLD6") (pinfunction "SHLD_SHLD6") (pintype "bidirectional"))
      (node (ref "USB1") (pin "SHLD7") (pinfunction "SHLD_SHLD7") (pintype "bidirectional"))
      (node (ref "USB1") (pin "SHLD8") (pinfunction "SHLD_SHLD8") (pintype "bidirectional"))
    )
    (net (code "28") (name "Net-(D2-P$2)") (class "Default")
      (node (ref "D2") (pin "2") (pinfunction "P$2_2") (pintype "bidirectional"))
      (node (ref "JTAG") (pin "1") (pinfunction "1_1") (pintype "bidirectional"))
    )
    (net (code "29") (name "Net-(D4-Pad2)") (class "Default")
      (node (ref "D4") (pin "2") (pinfunction "2_2") (pintype "bidirectional"))
      (node (ref "J1") (pin "1") (pinfunction "1_1") (pintype "passive"))
      (node (ref "R23") (pin "2") (pinfunction "2_2") (pintype "passive"))
    )
    (net (code "30") (name "Net-(D17-PadC)") (class "Default")
      (node (ref "D17") (pin "C") (pinfunction "C_C") (pintype "passive"))
      (node (ref "F5") (pin "1") (pinfunction "1_1") (pintype "passive"))
      (node (ref "J2") (pin "1") (pinfunction "1_1") (pintype "passive"))
    )
    (net (code "31") (name "Net-(F5-Pad2)") (class "Default")
      (node (ref "F5") (pin "2") (pinfunction "2_2") (pintype "passive"))
      (node (ref "Q2") (pin "3") (pinfunction "3_3") (pintype "bidirectional"))
    )
    (net (code "32") (name "Net-(J1-Pad3)") (class "Default")
      (node (ref "J1") (pin "3") (pinfunction "3_3") (pintype "passive"))
      (node (ref "Q5") (pin "3") (pinfunction "3_3") (pintype "bidirectional"))
    )
    (net (code "33") (name "Net-(J3-Pad29)") (class "Default")
      (node (ref "J3") (pin "29") (pinfunction "29_29") (pintype "passive"))
      (node (ref "JP4") (pin "1") (pinfunction "1_1") (pintype "bidirectional"))
    )
    (net (code "34") (name "Net-(J6-5DC-Pad3)") (class "Default")
      (node (ref "J6") (pin "3") (pinfunction "5DC_3") (pintype "passive"))
      (node (ref "J6") (pin "@3") (pinfunction "5DC_@3") (pintype "passive"))
      (node (ref "J6") (pin "P$3") (pinfunction "5DC_P$3") (pintype "passive"))
    )
    (net (code "35") (name "Net-(J6-5DC-Pad4)") (class "Default")
      (node (ref "J6") (pin "4") (pinfunction "5DC_4") (pintype "passive"))
      (node (ref "J6") (pin "@4") (pinfunction "5DC_@4") (pintype "passive"))
      (node (ref "J6") (pin "P$4") (pinfunction "5DC_P$4") (pintype "passive"))
    )
    (net (code "36") (name "Net-(J6-ENABLE-Pad25)") (class "Default")
      (node (ref "J6") (pin "25") (pinfunction "ENABLE_25") (pintype "passive"))
      (node (ref "J6") (pin "@25") (pinfunction "ENABLE_@25") (pintype "passive"))
      (node (ref "J6") (pin "P$25") (pinfunction "ENABLE_P$25") (pintype "passive"))
    )
    (net (code "37") (name "Net-(J6-PG-Pad24)") (class "Default")
      (node (ref "J6") (pin "24") (pinfunction "PG_24") (pintype "passive"))
      (node (ref "J6") (pin "@24") (pinfunction "PG_@24") (pintype "passive"))
      (node (ref "J6") (pin "P$24") (pinfunction "PG_P$24") (pintype "passive"))
      (node (ref "R21") (pin "1") (pinfunction "1_1") (pintype "passive"))
    )
    (net (code "38") (name "Net-(J18-PadSWCLK)") (class "Default")
      (node (ref "J18") (pin "SWCLK") (pinfunction "SWCLK_SWCLK") (pintype "power_in"))
      (node (ref "JTAG") (pin "4") (pinfunction "4_4") (pintype "bidirectional"))
    )
    (net (code "39") (name "Net-(J18-PadSWDIO)") (class "Default")
      (node (ref "J18") (pin "SWDIO") (pinfunction "SWDIO_SWDIO") (pintype "power_in"))
      (node (ref "JTAG") (pin "2") (pinfunction "2_2") (pintype "bidirectional"))
    )
    (net (code "40") (name "Net-(J18-PadSWO)") (class "Default")
      (node (ref "J18") (pin "SWO") (pinfunction "SWO_SWO") (pintype "power_in"))
      (node (ref "JTAG") (pin "6") (pinfunction "6_6") (pintype "bidirectional"))
    )
    (net (code "41") (name "Net-(J21-Pad2)") (class "Default")
      (node (ref "J21") (pin "2") (pinfunction "2_2") (pintype "bidirectional"))
      (node (ref "RT1") (pin "1") (pinfunction "1_1") (pintype "bidirectional"))
      (node (ref "RT2") (pin "2") (pinfunction "2_2") (pintype "bidirectional"))
      (node (ref "TP2") (pin "1") (pinfunction "1_1") (pintype "bidirectional"))
      (node (ref "TP5") (pin "1") (pinfunction "1_1") (pintype "bidirectional"))
    )
    (net (code "42") (name "Net-(JP5-Pad2)") (class "Default")
      (node (ref "JP5") (pin "2") (pinfunction "2_2") (pintype "passive"))
      (node (ref "MS1") (pin "1") (pinfunction "~{RST}_1") (pintype "input"))
      (node (ref "MS1") (pin "1'") (pinfunction "~{RST}_1'") (pintype "input"))
    )
    (net (code "43") (name "Net-(JP6-Pad2)") (class "Default")
      (node (ref "JP6") (pin "2") (pinfunction "2_2") (pintype "passive"))
      (node (ref "MS1") (pin "5") (pinfunction "A0_5") (pintype "bidirectional"))
      (node (ref "MS1") (pin "5'") (pinfunction "A0_5'") (pintype "bidirectional"))
    )
    (net (code "44") (name "Net-(JP7-Pad2)") (class "Default")
      (node (ref "JP7") (pin "2") (pinfunction "2_2") (pintype "passive"))
      (node (ref "MS1") (pin "6") (pinfunction "A1_6") (pintype "bidirectional"))
      (node (ref "MS1") (pin "6'") (pinfunction "A1_6'") (pintype "bidirectional"))
    )
    (net (code "45") (name "Net-(JP8-Pad2)") (class "Default")
      (node (ref "JP8") (pin "2") (pinfunction "2_2") (pintype "passive"))
      (node (ref "MS1") (pin "7") (pinfunction "A2_7") (pintype "bidirectional"))
      (node (ref "MS1") (pin "7'") (pinfunction "A2_7'") (pintype "bidirectional"))
    )
    (net (code "46") (name "Net-(JP9-Pad2)") (class "Default")
      (node (ref "JP9") (pin "2") (pinfunction "2_2") (pintype "passive"))
      (node (ref "MS1") (pin "8") (pinfunction "A3_8") (pintype "bidirectional"))
      (node (ref "MS1") (pin "8'") (pinfunction "A3_8'") (pintype "bidirectional"))
    )
    (net (code "47") (name "Net-(JP10-Pad2)") (class "Default")
      (node (ref "JP10") (pin "2") (pinfunction "2_2") (pintype "passive"))
      (node (ref "MS1") (pin "9") (pinfunction "A4_9") (pintype "bidirectional"))
      (node (ref "MS1") (pin "9'") (pinfunction "A4_9'") (pintype "bidirectional"))
    )
    (net (code "48") (name "Net-(JP11-Pad2)") (class "Default")
      (node (ref "JP11") (pin "2") (pinfunction "2_2") (pintype "passive"))
      (node (ref "MS1") (pin "10") (pinfunction "A5_10") (pintype "bidirectional"))
      (node (ref "MS1") (pin "10'") (pinfunction "A5_10'") (pintype "bidirectional"))
    )
    (net (code "49") (name "Net-(JP12-Pad2)") (class "Default")
      (node (ref "JP12") (pin "2") (pinfunction "2_2") (pintype "passive"))
      (node (ref "MS1") (pin "11") (pinfunction "SCK_11") (pintype "bidirectional"))
      (node (ref "MS1") (pin "11'") (pinfunction "SCK_11'") (pintype "bidirectional"))
    )
    (net (code "50") (name "Net-(JP13-Pad2)") (class "Default")
      (node (ref "JP13") (pin "2") (pinfunction "2_2") (pintype "passive"))
      (node (ref "MS1") (pin "12") (pinfunction "MOSI_12") (pintype "bidirectional"))
      (node (ref "MS1") (pin "12'") (pinfunction "MOSI_12'") (pintype "bidirectional"))
    )
    (net (code "51") (name "Net-(JP14-Pad2)") (class "Default")
      (node (ref "JP14") (pin "2") (pinfunction "2_2") (pintype "passive"))
      (node (ref "MS1") (pin "13") (pinfunction "MISO_13") (pintype "bidirectional"))
      (node (ref "MS1") (pin "13'") (pinfunction "MISO_13'") (pintype "bidirectional"))
    )
    (net (code "52") (name "Net-(JP15-Pad2)") (class "Default")
      (node (ref "JP15") (pin "2") (pinfunction "2_2") (pintype "passive"))
      (node (ref "MS1") (pin "14") (pinfunction "RX_14") (pintype "bidirectional"))
      (node (ref "MS1") (pin "14'") (pinfunction "RX_14'") (pintype "bidirectional"))
    )
    (net (code "53") (name "Net-(JP16-Pad2)") (class "Default")
      (node (ref "JP16") (pin "2") (pinfunction "2_2") (pintype "passive"))
      (node (ref "MS1") (pin "15") (pinfunction "TX_15") (pintype "bidirectional"))
      (node (ref "MS1") (pin "15'") (pinfunction "TX_15'") (pintype "bidirectional"))
    )
    (net (code "54") (name "Net-(JP17-Pad1)") (class "Default")
      (node (ref "JP17") (pin "1") (pinfunction "1_1") (pintype "passive"))
      (node (ref "MS1") (pin "28") (pinfunction "LI+_28") (pintype "power_in"))
      (node (ref "MS1") (pin "28'") (pinfunction "LI+_28'") (pintype "power_in"))
    )
    (net (code "55") (name "Net-(JP19-Pad1)") (class "Default")
      (node (ref "JP19") (pin "1") (pinfunction "1_1") (pintype "passive"))
      (node (ref "MS1") (pin "26") (pinfunction "VUSB_26") (pintype "power_in"))
      (node (ref "MS1") (pin "26'") (pinfunction "VUSB_26'") (pintype "power_in"))
    )
    (net (code "56") (name "Net-(JP20-Pad1)") (class "Default")
      (node (ref "JP20") (pin "1") (pinfunction "1_1") (pintype "passive"))
      (node (ref "MS1") (pin "25") (pinfunction "D8_25") (pintype "bidirectional"))
      (node (ref "MS1") (pin "25'") (pinfunction "D8_25'") (pintype "bidirectional"))
    )
    (net (code "57") (name "Net-(JP21-Pad1)") (class "Default")
      (node (ref "JP21") (pin "1") (pinfunction "1_1") (pintype "passive"))
      (node (ref "MS1") (pin "24") (pinfunction "D7_24") (pintype "bidirectional"))
      (node (ref "MS1") (pin "24'") (pinfunction "D7_24'") (pintype "bidirectional"))
    )
    (net (code "58") (name "Net-(JP22-Pad1)") (class "Default")
      (node (ref "JP22") (pin "1") (pinfunction "1_1") (pintype "passive"))
      (node (ref "MS1") (pin "23") (pinfunction "D6_23") (pintype "bidirectional"))
      (node (ref "MS1") (pin "23'") (pinfunction "D6_23'") (pintype "bidirectional"))
    )
    (net (code "59") (name "Net-(JP23-Pad1)") (class "Default")
      (node (ref "JP23") (pin "1") (pinfunction "1_1") (pintype "passive"))
      (node (ref "MS1") (pin "22") (pinfunction "D5_22") (pintype "bidirectional"))
      (node (ref "MS1") (pin "22'") (pinfunction "D5_22'") (pintype "bidirectional"))
    )
    (net (code "60") (name "Net-(JP24-Pad1)") (class "Default")
      (node (ref "JP24") (pin "1") (pinfunction "1_1") (pintype "passive"))
      (node (ref "MS1") (pin "21") (pinfunction "D4_21") (pintype "bidirectional"))
      (node (ref "MS1") (pin "21'") (pinfunction "D4_21'") (pintype "bidirectional"))
    )
    (net (code "61") (name "Net-(JP25-Pad1)") (class "Default")
      (node (ref "JP25") (pin "1") (pinfunction "1_1") (pintype "passive"))
      (node (ref "MS1") (pin "20") (pinfunction "D3_20") (pintype "bidirectional"))
      (node (ref "MS1") (pin "20'") (pinfunction "D3_20'") (pintype "bidirectional"))
    )
    (net (code "62") (name "Net-(JP26-Pad1)") (class "Default")
      (node (ref "JP26") (pin "1") (pinfunction "1_1") (pintype "passive"))
      (node (ref "MS1") (pin "19") (pinfunction "D2_19") (pintype "bidirectional"))
      (node (ref "MS1") (pin "19'") (pinfunction "D2_19'") (pintype "bidirectional"))
    )
    (net (code "63") (name "Net-(JP27-Pad1)") (class "Default")
      (node (ref "JP27") (pin "1") (pinfunction "1_1") (pintype "passive"))
      (node (ref "MS1") (pin "18") (pinfunction "SCL_18") (pintype "bidirectional"))
      (node (ref "MS1") (pin "18'") (pinfunction "SCL_18'") (pintype "bidirectional"))
    )
    (net (code "64") (name "Net-(JP28-Pad1)") (class "Default")
      (node (ref "JP28") (pin "1") (pinfunction "1_1") (pintype "passive"))
      (node (ref "MS1") (pin "17") (pinfunction "SDA_17") (pintype "bidirectional"))
      (node (ref "MS1") (pin "17'") (pinfunction "SDA_17'") (pintype "bidirectional"))
    )
    (net (code "65") (name "Net-(LED1-A)") (class "Default")
      (node (ref "LED1") (pin "1") (pinfunction "A_1") (pintype "bidirectional"))
      (node (ref "R16") (pin "2") (pinfunction "2_2") (pintype "passive"))
      (node (ref "R18") (pin "1") (pinfunction "1_1") (pintype "passive"))
    )
    (net (code "66") (name "Net-(LED1-K)") (class "Default")
      (node (ref "LED1") (pin "2") (pinfunction "K_2") (pintype "bidirectional"))
      (node (ref "Q1") (pin "3") (pinfunction "3_3") (pintype "bidirectional"))
      (node (ref "R22") (pin "2") (pinfunction "2_2") (pintype "passive"))
    )
    (net (code "67") (name "Net-(LED2-A)") (class "Default")
      (node (ref "JP1") (pin "2") (pinfunction "2_2") (pintype "passive"))
      (node (ref "LED2") (pin "1") (pinfunction "A_1") (pintype "bidirectional"))
    )
    (net (code "68") (name "Net-(LED2-K)") (class "Default")
      (node (ref "LED2") (pin "2") (pinfunction "K_2") (pintype "bidirectional"))
      (node (ref "R24") (pin "2") (pinfunction "2_2") (pintype "passive"))
    )
    (net (code "69") (name "Net-(LED3-K)") (class "Default")
      (node (ref "LED3") (pin "2") (pinfunction "K_2") (pintype "bidirectional"))
      (node (ref "R13") (pin "1") (pinfunction "1_1") (pintype "bidirectional"))
    )
    (net (code "70") (name "Net-(MS1-MD-Pad3')") (class "Default")
      (node (ref "MS1") (pin "3") (pinfunction "MD_3") (pintype "bidirectional"))
      (node (ref "MS1") (pin "3'") (pinfunction "MD_3'") (pintype "bidirectional"))
    )
    (net (code "71") (name "Net-(Q1-Pad1)") (class "Default")
      (node (ref "Q1") (pin "1") (pinfunction "1_1") (pintype "bidirectional"))
      (node (ref "R11") (pin "1") (pinfunction "1_1") (pintype "passive"))
      (node (ref "R17") (pin "2") (pinfunction "2_2") (pintype "passive"))
    )
    (net (code "72") (name "Net-(Q2-Pad1)") (class "Default")
      (node (ref "Q2") (pin "1") (pinfunction "1_1") (pintype "bidirectional"))
      (node (ref "Q4") (pin "1") (pinfunction "1_1") (pintype "bidirectional"))
      (node (ref "R14") (pin "2") (pinfunction "2_2") (pintype "passive"))
      (node (ref "R15") (pin "2") (pinfunction "2_2") (pintype "passive"))
    )
    (net (code "73") (name "Net-(Q2-Pad2)") (class "Default")
      (node (ref "Q2") (pin "2") (pinfunction "2_2") (pintype "bidirectional"))
      (node (ref "Q4") (pin "2") (pinfunction "2_2") (pintype "bidirectional"))
      (node (ref "R14") (pin "1") (pinfunction "1_1") (pintype "passive"))
      (node (ref "R32") (pin "1") (pinfunction "1_1") (pintype "passive"))
    )
    (net (code "74") (name "Net-(Q3-Pad1)") (class "Default")
      (node (ref "Q3") (pin "1") (pinfunction "1_1") (pintype "bidirectional"))
      (node (ref "Q5") (pin "1") (pinfunction "1_1") (pintype "bidirectional"))
      (node (ref "R30") (pin "1") (pinfunction "1_1") (pintype "passive"))
      (node (ref "R31") (pin "1") (pinfunction "1_1") (pintype "bidirectional"))
    )
    (net (code "75") (name "Net-(Q3-Pad2)") (class "Default")
      (node (ref "Q3") (pin "2") (pinfunction "2_2") (pintype "bidirectional"))
      (node (ref "Q5") (pin "2") (pinfunction "2_2") (pintype "bidirectional"))
      (node (ref "R30") (pin "2") (pinfunction "2_2") (pintype "passive"))
      (node (ref "R33") (pin "2") (pinfunction "2_2") (pintype "bidirectional"))
    )
    (net (code "76") (name "Net-(R15-Pad1)") (class "Default")
      (node (ref "R15") (pin "1") (pinfunction "1_1") (pintype "passive"))
      (node (ref "S1") (pin "2") (pinfunction "2_2") (pintype "bidirectional"))
      (node (ref "S1") (pin "5") (pinfunction "5_5") (pintype "bidirectional"))
    )
    (net (code "77") (name "Net-(R31-Pad2)") (class "Default")
      (node (ref "R31") (pin "2") (pinfunction "2_2") (pintype "bidirectional"))
      (node (ref "S4") (pin "2") (pinfunction "2_2") (pintype "bidirectional"))
      (node (ref "S4") (pin "5") (pinfunction "5_5") (pintype "bidirectional"))
    )
    (net (code "78") (name "Net-(R32-Pad2)") (class "Default")
      (node (ref "R32") (pin "2") (pinfunction "2_2") (pintype "passive"))
      (node (ref "S1") (pin "1") (pinfunction "1_1") (pintype "bidirectional"))
      (node (ref "S1") (pin "4") (pinfunction "4_4") (pintype "bidirectional"))
    )
    (net (code "79") (name "Net-(R33-Pad1)") (class "Default")
      (node (ref "R33") (pin "1") (pinfunction "1_1") (pintype "bidirectional"))
      (node (ref "S4") (pin "1") (pinfunction "1_1") (pintype "bidirectional"))
      (node (ref "S4") (pin "4") (pinfunction "4_4") (pintype "bidirectional"))
    )
    (net (code "80") (name "Net-(RGB-2)") (class "Default")
      (node (ref "R8") (pin "2") (pinfunction "2_2") (pintype "passive"))
      (node (ref "RGB") (pin "BLUE") (pinfunction "2_BLUE") (pintype "passive"))
    )
    (net (code "81") (name "Net-(RGB-3)") (class "Default")
      (node (ref "R19") (pin "2") (pinfunction "2_2") (pintype "passive"))
      (node (ref "RGB") (pin "GREEN") (pinfunction "3_GREEN") (pintype "passive"))
    )
    (net (code "82") (name "Net-(RGB-4)") (class "Default")
      (node (ref "R20") (pin "2") (pinfunction "2_2") (pintype "passive"))
      (node (ref "RGB") (pin "RED") (pinfunction "4_RED") (pintype "passive"))
    )
    (net (code "83") (name "Net-(U1-CE)") (class "Default")
      (node (ref "R2") (pin "1") (pinfunction "1_1") (pintype "passive"))
      (node (ref "R7") (pin "1") (pinfunction "1_1") (pintype "passive"))
      (node (ref "U1") (pin "4") (pinfunction "CE_4") (pintype "bidirectional"))
    )
    (net (code "84") (name "Net-(USB1-CC1)") (class "Default")
      (node (ref "R6") (pin "1") (pinfunction "1_1") (pintype "passive"))
      (node (ref "USB1") (pin "A5") (pinfunction "CC1_A5") (pintype "bidirectional"))
    )
    (net (code "85") (name "Net-(USB1-CC2)") (class "Default")
      (node (ref "R9") (pin "1") (pinfunction "1_1") (pintype "passive"))
      (node (ref "USB1") (pin "B5") (pinfunction "CC2_B5") (pintype "bidirectional"))
    )
    (net (code "86") (name "Net-(USB2-CC1)") (class "Default")
      (node (ref "R1") (pin "1") (pinfunction "1_1") (pintype "passive"))
      (node (ref "USB2") (pin "A5") (pinfunction "CC1_A5") (pintype "bidirectional"))
    )
    (net (code "87") (name "Net-(USB2-CC2)") (class "Default")
      (node (ref "R3") (pin "1") (pinfunction "1_1") (pintype "passive"))
      (node (ref "USB2") (pin "B5") (pinfunction "CC2_B5") (pintype "bidirectional"))
    )
    (net (code "88") (name "PWM0") (class "Default")
      (node (ref "J18") (pin "66") (pinfunction "D4_66") (pintype "bidirectional"))
      (node (ref "J3") (pin "52") (pinfunction "52_52") (pintype "passive"))
      (node (ref "JP24") (pin "2") (pinfunction "2_2") (pintype "passive"))
    )
    (net (code "89") (name "PWM1") (class "Default")
      (node (ref "J18") (pin "68") (pinfunction "D5_68") (pintype "bidirectional"))
      (node (ref "J3") (pin "54") (pinfunction "54_54") (pintype "passive"))
      (node (ref "JP20") (pin "2") (pinfunction "2_2") (pintype "passive"))
    )
    (net (code "90") (name "PWM2") (class "Default")
      (node (ref "J18") (pin "70") (pinfunction "D6_70") (pintype "bidirectional"))
      (node (ref "J3") (pin "56") (pinfunction "56_56") (pintype "passive"))
      (node (ref "JP22") (pin "2") (pinfunction "2_2") (pintype "passive"))
    )
    (net (code "91") (name "PWM3") (class "Default")
      (node (ref "J18") (pin "72") (pinfunction "D7_72") (pintype "bidirectional"))
      (node (ref "J3") (pin "58") (pinfunction "58_58") (pintype "passive"))
      (node (ref "JP21") (pin "2") (pinfunction "2_2") (pintype "passive"))
    )
    (net (code "92") (name "REGN") (class "Default")
      (node (ref "J6") (pin "8") (pinfunction "NC_8") (pintype "passive"))
      (node (ref "J6") (pin "@8") (pinfunction "NC_@8") (pintype "passive"))
      (node (ref "J6") (pin "P$8") (pinfunction "NC_P$8") (pintype "passive"))
      (node (ref "RT1") (pin "2") (pinfunction "2_2") (pintype "bidirectional"))
      (node (ref "TP1") (pin "1") (pinfunction "1_1") (pintype "bidirectional"))
    )
    (net (code "93") (name "RTS") (class "Default")
      (node (ref "J18") (pin "42") (pinfunction "RTS_42") (pintype "bidirectional"))
      (node (ref "J3") (pin "28") (pinfunction "28_28") (pintype "passive"))
    )
    (net (code "94") (name "RX") (class "Default")
      (node (ref "J18") (pin "38") (pinfunction "RXD_38") (pintype "bidirectional"))
      (node (ref "J3") (pin "24") (pinfunction "24_24") (pintype "passive"))
      (node (ref "JP15") (pin "1") (pinfunction "1_1") (pintype "passive"))
    )
    (net (code "95") (name "SCK") (class "Default")
      (node (ref "J18") (pin "54") (pinfunction "SCLK_54") (pintype "bidirectional"))
      (node (ref "J3") (pin "40") (pinfunction "40_40") (pintype "passive"))
      (node (ref "JP12") (pin "1") (pinfunction "1_1") (pintype "passive"))
    )
    (net (code "96") (name "SCL") (class "Default")
      (node (ref "J18") (pin "20") (pinfunction "SCL_20") (pintype "bidirectional"))
      (node (ref "J3") (pin "14") (pinfunction "14_14") (pintype "passive"))
      (node (ref "J4") (pin "4") (pinfunction "4_4") (pintype "passive"))
      (node (ref "J6") (pin "14") (pinfunction "SCL_14") (pintype "passive"))
      (node (ref "J6") (pin "@14") (pinfunction "SCL_@14") (pintype "passive"))
      (node (ref "J6") (pin "P$14") (pinfunction "SCL_P$14") (pintype "passive"))
      (node (ref "JP27") (pin "2") (pinfunction "2_2") (pintype "passive"))
    )
    (net (code "97") (name "SDA") (class "Default")
      (node (ref "J18") (pin "22") (pinfunction "SDA_22") (pintype "bidirectional"))
      (node (ref "J3") (pin "16") (pinfunction "16_16") (pintype "passive"))
      (node (ref "J4") (pin "3") (pinfunction "3_3") (pintype "passive"))
      (node (ref "J6") (pin "15") (pinfunction "SDA_15") (pintype "passive"))
      (node (ref "J6") (pin "@15") (pinfunction "SDA_@15") (pintype "passive"))
      (node (ref "J6") (pin "P$15") (pinfunction "SDA_P$15") (pintype "passive"))
      (node (ref "JP28") (pin "2") (pinfunction "2_2") (pintype "passive"))
    )
    (net (code "98") (name "SOM5") (class "Default")
      (node (ref "J18") (pin "67") (pinfunction "SIM_VCC_67") (pintype "power_in"))
      (node (ref "J3") (pin "51") (pinfunction "51_51") (pintype "passive"))
    )
    (net (code "99") (name "SOM6") (class "Default")
      (node (ref "J18") (pin "69") (pinfunction "SIM_RST_69") (pintype "bidirectional"))
      (node (ref "J3") (pin "53") (pinfunction "53_53") (pintype "passive"))
    )
    (net (code "100") (name "SOM7") (class "Default")
      (node (ref "J18") (pin "71") (pinfunction "SIM_CLK_71") (pintype "bidirectional"))
      (node (ref "J3") (pin "55") (pinfunction "55_55") (pintype "passive"))
    )
    (net (code "101") (name "SOM8") (class "Default")
      (node (ref "J18") (pin "73") (pinfunction "SIM_DATA_73") (pintype "bidirectional"))
      (node (ref "J3") (pin "57") (pinfunction "57_57") (pintype "passive"))
    )
    (net (code "102") (name "SOM9") (class "Default")
      (node (ref "J18") (pin "75") (pinfunction "NC_75") (pintype "bidirectional"))
      (node (ref "J3") (pin "60") (pinfunction "60_60") (pintype "passive"))
    )
    (net (code "103") (name "SOM10") (class "Default")
      (node (ref "J18") (pin "14") (pinfunction "NC_14") (pintype "bidirectional"))
      (node (ref "J3") (pin "10") (pinfunction "10_10") (pintype "passive"))
    )
    (net (code "104") (name "SOM11") (class "Default")
      (node (ref "J18") (pin "18") (pinfunction "GNSS_TXD_18") (pintype "bidirectional"))
      (node (ref "J3") (pin "12") (pinfunction "12_12") (pintype "passive"))
    )
    (net (code "105") (name "SOM12") (class "Default")
      (node (ref "J18") (pin "58") (pinfunction "D24_58") (pintype "bidirectional"))
      (node (ref "J3") (pin "44") (pinfunction "44_44") (pintype "passive"))
    )
    (net (code "106") (name "SOM13") (class "Default")
      (node (ref "J18") (pin "60") (pinfunction "D25_60") (pintype "bidirectional"))
      (node (ref "J3") (pin "46") (pinfunction "46_46") (pintype "passive"))
    )
    (net (code "107") (name "SOM14") (class "Default")
      (node (ref "J18") (pin "51") (pinfunction "NC_51") (pintype "bidirectional"))
      (node (ref "J3") (pin "35") (pinfunction "35_35") (pintype "passive"))
    )
    (net (code "108") (name "SOM15") (class "Default")
      (node (ref "J18") (pin "53") (pinfunction "SWD_CLK_53") (pintype "bidirectional"))
      (node (ref "J3") (pin "37") (pinfunction "37_37") (pintype "passive"))
    )
    (net (code "109") (name "SOM16") (class "Default")
      (node (ref "J18") (pin "55") (pinfunction "SWD_DATA_55") (pintype "bidirectional"))
      (node (ref "J3") (pin "39") (pinfunction "39_39") (pintype "passive"))
    )
    (net (code "110") (name "SOM17") (class "Default")
      (node (ref "J18") (pin "57") (pinfunction "D27_57") (pintype "bidirectional"))
      (node (ref "J3") (pin "41") (pinfunction "41_41") (pintype "bidirectional"))
    )
    (net (code "111") (name "SOM18") (class "Default")
      (node (ref "J18") (pin "59") (pinfunction "D26_59") (pintype "bidirectional"))
      (node (ref "J3") (pin "43") (pinfunction "43_43") (pintype "passive"))
    )
    (net (code "112") (name "TS") (class "Default")
      (node (ref "J21") (pin "1") (pinfunction "1_1") (pintype "bidirectional"))
      (node (ref "J6") (pin "17") (pinfunction "TS_17") (pintype "passive"))
      (node (ref "J6") (pin "@17") (pinfunction "TS_@17") (pintype "passive"))
      (node (ref "J6") (pin "P$17") (pinfunction "TS_P$17") (pintype "passive"))
      (node (ref "R23") (pin "1") (pinfunction "1_1") (pintype "passive"))
    )
    (net (code "113") (name "TX") (class "Default")
      (node (ref "J18") (pin "36") (pinfunction "TXD_36") (pintype "bidirectional"))
      (node (ref "J3") (pin "22") (pinfunction "22_22") (pintype "passive"))
      (node (ref "JP16") (pin "1") (pinfunction "1_1") (pintype "passive"))
    )
    (net (code "114") (name "UB_USB_N") (class "Default")
      (node (ref "D23") (pin "1") (pinfunction "1_1") (pintype "bidirectional"))
      (node (ref "J18") (pin "46") (pinfunction "UB_USB_N_46") (pintype "bidirectional"))
      (node (ref "USB2") (pin "A7") (pinfunction "D-_A7") (pintype "bidirectional"))
      (node (ref "USB2") (pin "B7") (pinfunction "D-_B7") (pintype "bidirectional"))
    )
    (net (code "115") (name "UB_USB_P") (class "Default")
      (node (ref "D23") (pin "4") (pinfunction "4_4") (pintype "bidirectional"))
      (node (ref "J18") (pin "44") (pinfunction "UB_USB_P_44") (pintype "bidirectional"))
      (node (ref "USB2") (pin "A6") (pinfunction "D+_A6") (pintype "bidirectional"))
      (node (ref "USB2") (pin "B6") (pinfunction "D+_B6") (pintype "bidirectional"))
    )
    (net (code "116") (name "UB_VBUS") (class "Default")
      (node (ref "D23") (pin "5") (pinfunction "5_5") (pintype "bidirectional"))
      (node (ref "F4") (pin "P$2") (pinfunction "2_P$2") (pintype "bidirectional"))
      (node (ref "USB2") (pin "VBUS1") (pinfunction "VBUS_VBUS1") (pintype "bidirectional"))
      (node (ref "USB2") (pin "VBUS2") (pinfunction "VBUS_VBUS2") (pintype "bidirectional"))
    )
    (net (code "117") (name "UB_VBUS1") (class "Default")
      (node (ref "F4") (pin "P$1") (pinfunction "1_P$1") (pintype "bidirectional"))
      (node (ref "J18") (pin "74") (pinfunction "MODEM_VBUS_74") (pintype "power_in"))
    )
    (net (code "118") (name "USB_N") (class "Default")
      (node (ref "D1") (pin "1") (pinfunction "1_1") (pintype "bidirectional"))
      (node (ref "J18") (pin "13") (pinfunction "USB_N_13") (pintype "bidirectional"))
      (node (ref "USB1") (pin "A7") (pinfunction "D-_A7") (pintype "bidirectional"))
      (node (ref "USB1") (pin "B7") (pinfunction "D-_B7") (pintype "bidirectional"))
    )
    (net (code "119") (name "USB_P") (class "Default")
      (node (ref "D1") (pin "4") (pinfunction "4_4") (pintype "bidirectional"))
      (node (ref "J18") (pin "11") (pinfunction "USB_P_11") (pintype "bidirectional"))
      (node (ref "USB1") (pin "A6") (pinfunction "D+_A6") (pintype "bidirectional"))
      (node (ref "USB1") (pin "B6") (pinfunction "D+_B6") (pintype "bidirectional"))
    )
    (net (code "120") (name "VBAT") (class "Default")
      (node (ref "J6") (pin "18") (pinfunction "VBAT_18") (pintype "passive"))
      (node (ref "J6") (pin "19") (pinfunction "VBAT_19") (pintype "passive"))
      (node (ref "J6") (pin "20") (pinfunction "VBAT_20") (pintype "passive"))
      (node (ref "J6") (pin "@18") (pinfunction "VBAT_@18") (pintype "passive"))
      (node (ref "J6") (pin "@19") (pinfunction "VBAT_@19") (pintype "passive"))
      (node (ref "J6") (pin "@20") (pinfunction "VBAT_@20") (pintype "passive"))
      (node (ref "J6") (pin "P$18") (pinfunction "VBAT_P$18") (pintype "passive"))
      (node (ref "J6") (pin "P$19") (pinfunction "VBAT_P$19") (pintype "passive"))
      (node (ref "J6") (pin "P$20") (pinfunction "VBAT_P$20") (pintype "passive"))
      (node (ref "JP17") (pin "2") (pinfunction "2_2") (pintype "passive"))
      (node (ref "Q3") (pin "3") (pinfunction "3_3") (pintype "bidirectional"))
      (node (ref "VBAT") (pin "1") (pinfunction "TP_1") (pintype "bidirectional"))
    )
    (net (code "121") (name "VBUS") (class "Default")
      (node (ref "F2") (pin "P$2") (pinfunction "2_P$2") (pintype "bidirectional"))
      (node (ref "U1") (pin "5") (pinfunction "VIN_5") (pintype "power_in"))
    )
    (net (code "122") (name "VCC") (class "Default")
      (node (ref "C10") (pin "1") (pinfunction "1_1") (pintype "passive"))
      (node (ref "C20") (pin "1") (pinfunction "1_1") (pintype "passive"))
      (node (ref "C61") (pin "1") (pinfunction "1_1") (pintype "passive"))
      (node (ref "C8") (pin "1") (pinfunction "1_1") (pintype "passive"))
      (node (ref "C9") (pin "1") (pinfunction "1_1") (pintype "passive"))
      (node (ref "D16") (pin "2") (pinfunction "P$2_2") (pintype "bidirectional"))
      (node (ref "J18") (pin "2") (pinfunction "VCC_2") (pintype "power_in"))
      (node (ref "J18") (pin "4") (pinfunction "VCC_4") (pintype "power_in"))
      (node (ref "J18") (pin "6") (pinfunction "VCC_6") (pintype "power_in"))
      (node (ref "J18") (pin "8") (pinfunction "VCC_8") (pintype "power_in"))
      (node (ref "J3") (pin "2") (pinfunction "2_2") (pintype "passive"))
      (node (ref "J3") (pin "4") (pinfunction "4_4") (pintype "passive"))
      (node (ref "J3") (pin "6") (pinfunction "6_6") (pintype "passive"))
      (node (ref "J6") (pin "5") (pinfunction "VCC_5") (pintype "passive"))
      (node (ref "J6") (pin "6") (pinfunction "VCC_6") (pintype "passive"))
      (node (ref "J6") (pin "@5") (pinfunction "VCC_@5") (pintype "passive"))
      (node (ref "J6") (pin "@6") (pinfunction "VCC_@6") (pintype "passive"))
      (node (ref "J6") (pin "P$5") (pinfunction "VCC_P$5") (pintype "passive"))
      (node (ref "J6") (pin "P$6") (pinfunction "VCC_P$6") (pintype "passive"))
      (node (ref "VCC") (pin "1") (pinfunction "TP_1") (pintype "bidirectional"))
    )
    (net (code "123") (name "VIN") (class "Default")
      (node (ref "J6") (pin "11") (pinfunction "VIN_11") (pintype "passive"))
      (node (ref "J6") (pin "12") (pinfunction "VIN_12") (pintype "passive"))
      (node (ref "J6") (pin "@11") (pinfunction "VIN_@11") (pintype "passive"))
      (node (ref "J6") (pin "@12") (pinfunction "VIN_@12") (pintype "passive"))
      (node (ref "J6") (pin "P$11") (pinfunction "VIN_P$11") (pintype "passive"))
      (node (ref "J6") (pin "P$12") (pinfunction "VIN_P$12") (pintype "passive"))
      (node (ref "Q4") (pin "3") (pinfunction "3_3") (pintype "bidirectional"))
      (node (ref "R11") (pin "2") (pinfunction "2_2") (pintype "passive"))
      (node (ref "R18") (pin "2") (pinfunction "2_2") (pintype "passive"))
      (node (ref "VIN") (pin "1") (pinfunction "TP_1") (pintype "bidirectional"))
    )
    (net (code "124") (name "VUSB") (class "Default")
      (node (ref "D1") (pin "5") (pinfunction "5_5") (pintype "bidirectional"))
      (node (ref "F2") (pin "P$1") (pinfunction "1_P$1") (pintype "bidirectional"))
      (node (ref "USB1") (pin "VBUS1") (pinfunction "VBUS_VBUS1") (pintype "bidirectional"))
      (node (ref "USB1") (pin "VBUS2") (pinfunction "VBUS_VBUS2") (pintype "bidirectional"))
    )
    (net (code "125") (name "VUSB-MCU") (class "Default")
      (node (ref "J18") (pin "16") (pinfunction "NC_16") (pintype "power_in"))
      (node (ref "JP19") (pin "2") (pinfunction "2_2") (pintype "passive"))
      (node (ref "U1") (pin "1") (pinfunction "VOUT_1") (pintype "power_in"))
    )
    (net (code "126") (name "unconnected-(D1-Pad3)") (class "Default")
      (node (ref "D1") (pin "3") (pinfunction "3_3") (pintype "bidirectional"))
    )
    (net (code "127") (name "unconnected-(D1-Pad6)") (class "Default")
      (node (ref "D1") (pin "6") (pinfunction "6_6") (pintype "bidirectional"))
    )
    (net (code "128") (name "unconnected-(D23-Pad3)") (class "Default")
      (node (ref "D23") (pin "3") (pinfunction "3_3") (pintype "bidirectional"))
    )
    (net (code "129") (name "unconnected-(D23-Pad6)") (class "Default")
      (node (ref "D23") (pin "6") (pinfunction "6_6") (pintype "bidirectional"))
    )
    (net (code "130") (name "unconnected-(J3-Pad30)") (class "Default")
      (node (ref "J3") (pin "30") (pinfunction "30_30") (pintype "passive"))
    )
    (net (code "131") (name "unconnected-(J3-Pad32)") (class "Default")
      (node (ref "J3") (pin "32") (pinfunction "32_32") (pintype "passive"))
    )
    (net (code "132") (name "unconnected-(J11-5-PadNC1)") (class "Default")
      (node (ref "J11") (pin "NC1") (pinfunction "5_NC1") (pintype "bidirectional"))
    )
    (net (code "133") (name "unconnected-(J11-6-PadNC2)") (class "Default")
      (node (ref "J11") (pin "NC2") (pinfunction "6_NC2") (pintype "bidirectional"))
    )
    (net (code "134") (name "unconnected-(JTAG-Pad7)") (class "Default")
      (node (ref "JTAG") (pin "7") (pinfunction "7_7") (pintype "bidirectional"))
    )
    (net (code "135") (name "unconnected-(JTAG-Pad8)") (class "Default")
      (node (ref "JTAG") (pin "8") (pinfunction "8_8") (pintype "bidirectional"))
    )
    (net (code "136") (name "unconnected-(U1-FLG-Pad3)") (class "Default")
      (node (ref "U1") (pin "3") (pinfunction "FLG_3") (pintype "bidirectional"))
    )
    (net (code "137") (name "unconnected-(X1-Pad1)") (class "Default")
      (node (ref "X1") (pin "1") (pinfunction "1_1") (pintype "passive"))
    )
    (net (code "138") (name "unconnected-(X2-Pad1)") (class "Default")
      (node (ref "X2") (pin "1") (pinfunction "1_1") (pintype "passive"))
    )
    (net (code "139") (name "unconnected-(X3-Pad1)") (class "Default")
      (node (ref "X3") (pin "1") (pinfunction "1_1") (pintype "passive"))
    )
    (net (code "140") (name "~{MODE}") (class "Default")
      (node (ref "J18") (pin "32") (pinfunction "~{MODE}_32") (pintype "bidirectional"))
      (node (ref "J3") (pin "18") (pinfunction "18_18") (pintype "passive"))
      (node (ref "R12") (pin "1") (pinfunction "1_1") (pintype "passive"))
      (node (ref "S2") (pin "3") (pinfunction "3_3") (pintype "passive"))
      (node (ref "S2") (pin "4") (pinfunction "4_4") (pintype "passive"))
    )
    (net (code "141") (name "~{RESET}") (class "Default")
      (node (ref "C1") (pin "1") (pinfunction "1_1") (pintype "passive"))
      (node (ref "J18") (pin "!RESET") (pinfunction "~{RESET}_!RESET") (pintype "power_in"))
      (node (ref "J18") (pin "34") (pinfunction "~{RESET}_34") (pintype "bidirectional"))
      (node (ref "J3") (pin "20") (pinfunction "20_20") (pintype "passive"))
      (node (ref "J6") (pin "23") (pinfunction "~{RST}_23") (pintype "passive"))
      (node (ref "J6") (pin "@23") (pinfunction "~{RST}_@23") (pintype "passive"))
      (node (ref "J6") (pin "P$23") (pinfunction "~{RST}_P$23") (pintype "passive"))
      (node (ref "JP5") (pin "1") (pinfunction "1_1") (pintype "passive"))
      (node (ref "JTAG") (pin "10") (pinfunction "10_10") (pintype "bidirectional"))
      (node (ref "R4") (pin "1") (pinfunction "1_1") (pintype "passive"))
      (node (ref "S3") (pin "3") (pinfunction "3_3") (pintype "passive"))
      (node (ref "S3") (pin "4") (pinfunction "4_4") (pintype "passive"))
    )
  )
)
